# M868Hcjl.net
KiCad netlist of a schematic drawn in EAGLE
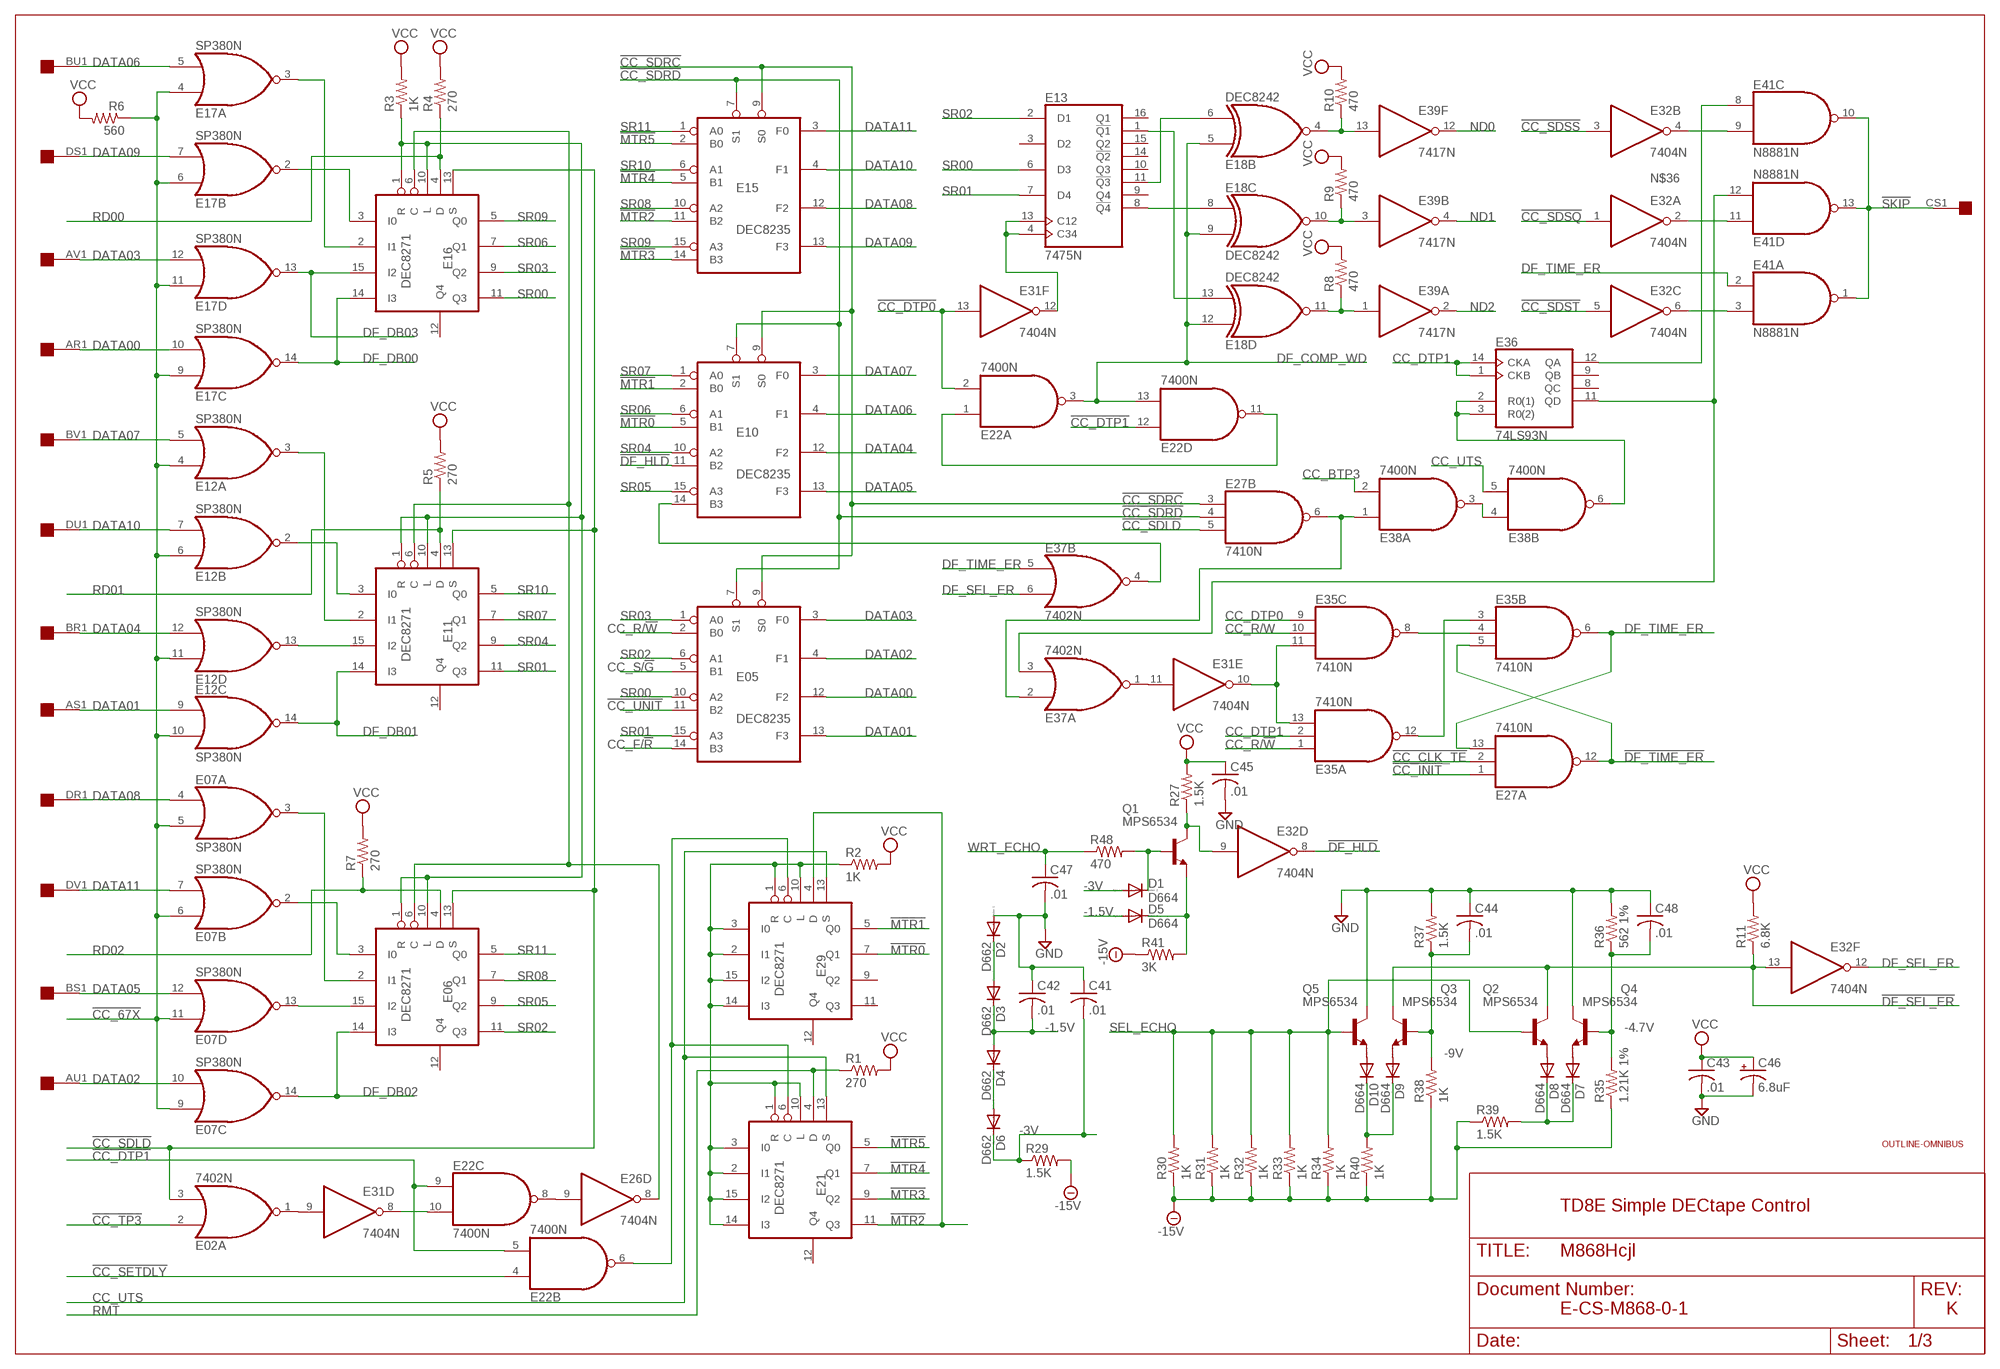
[diagram p0: schematic, sheet 1]
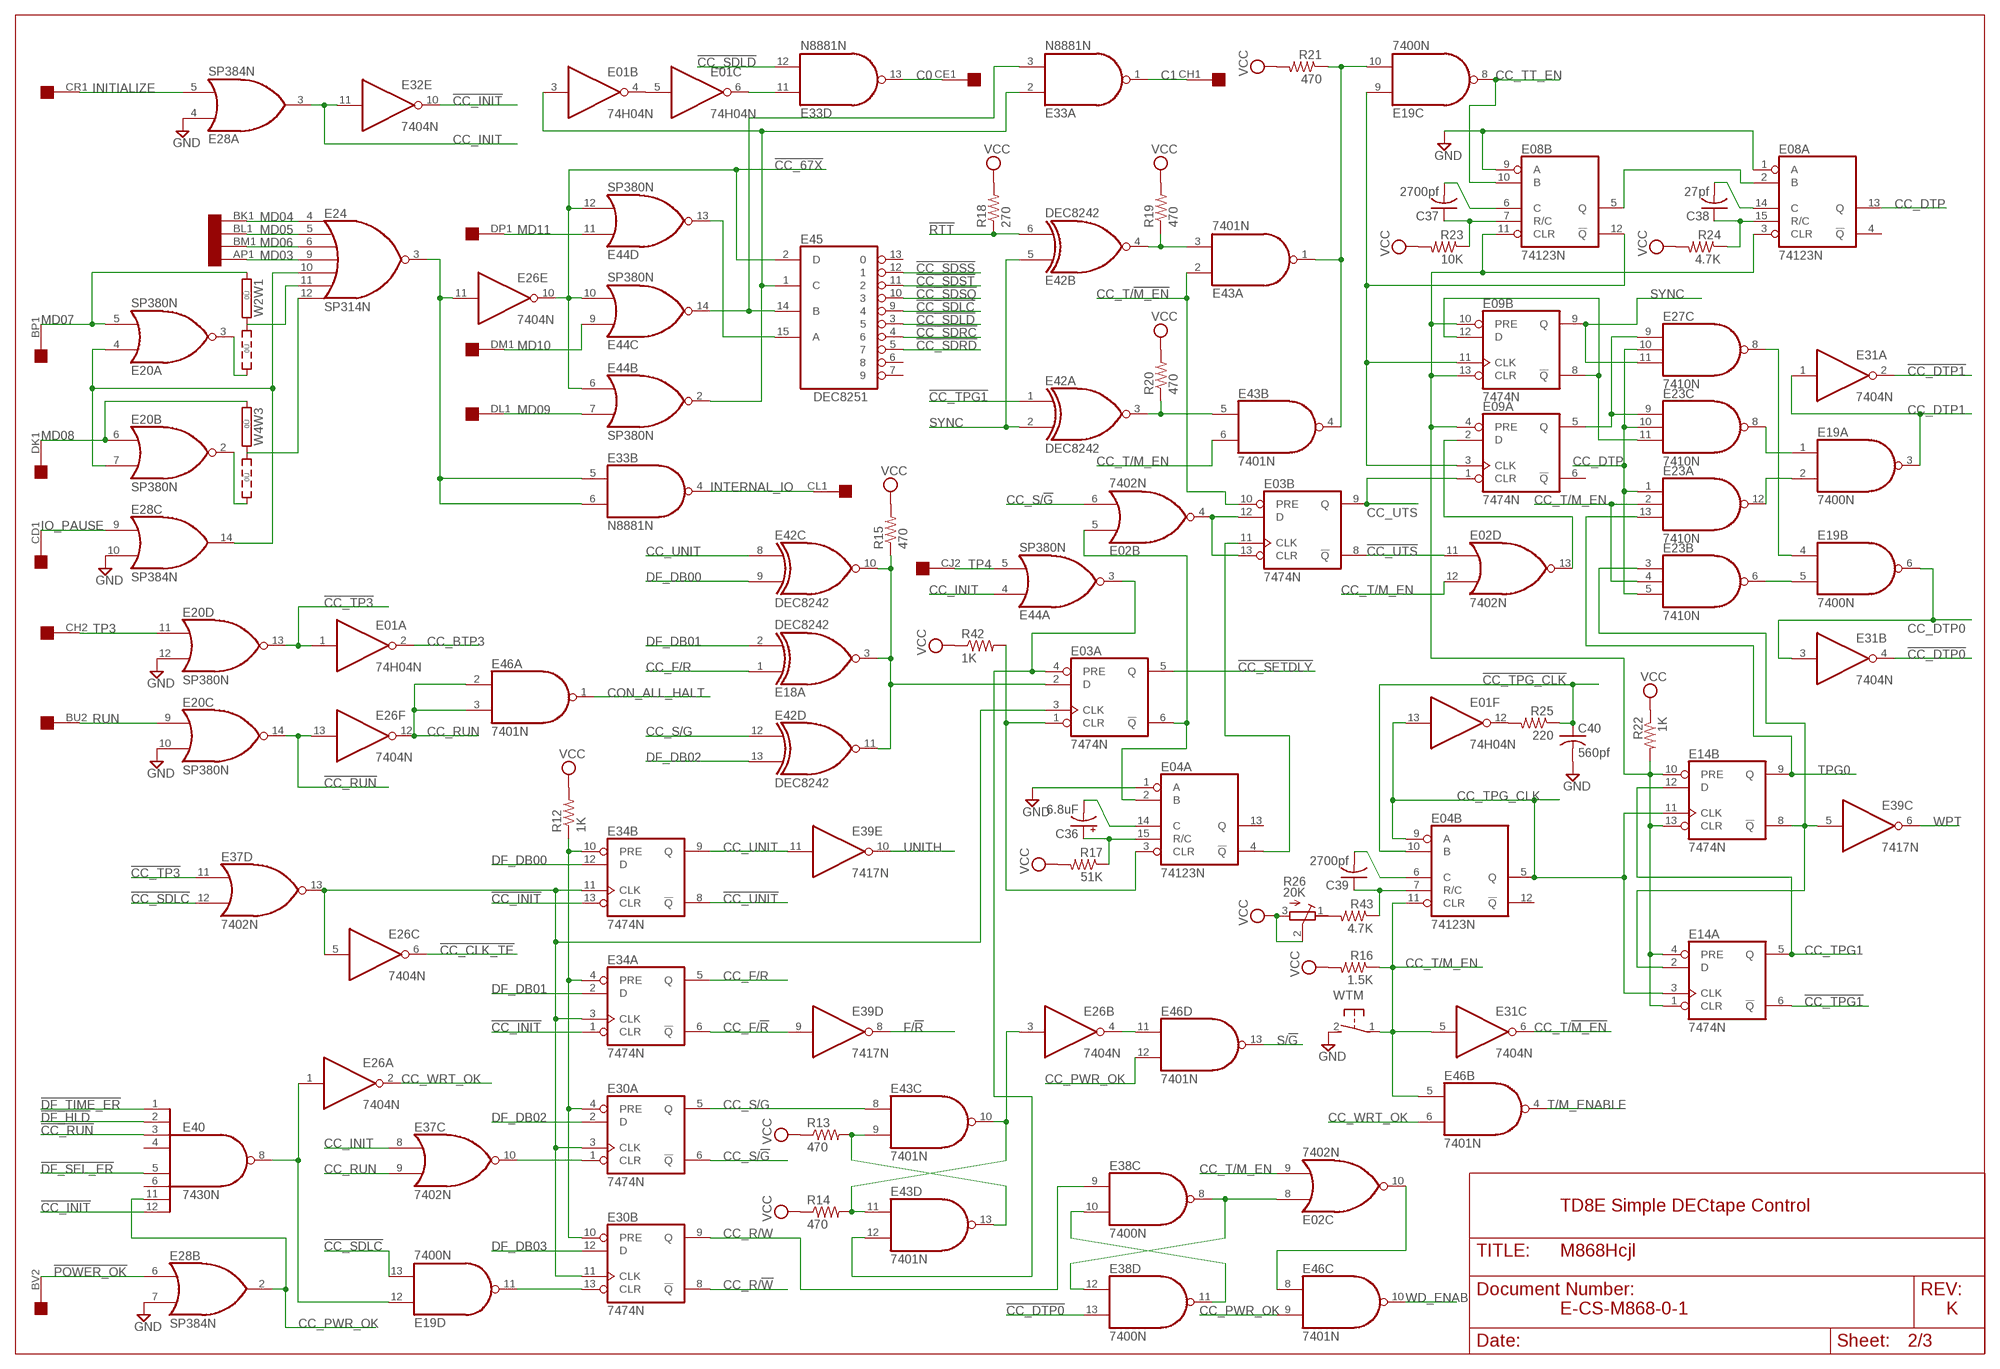
[diagram p1: schematic, sheet 2]
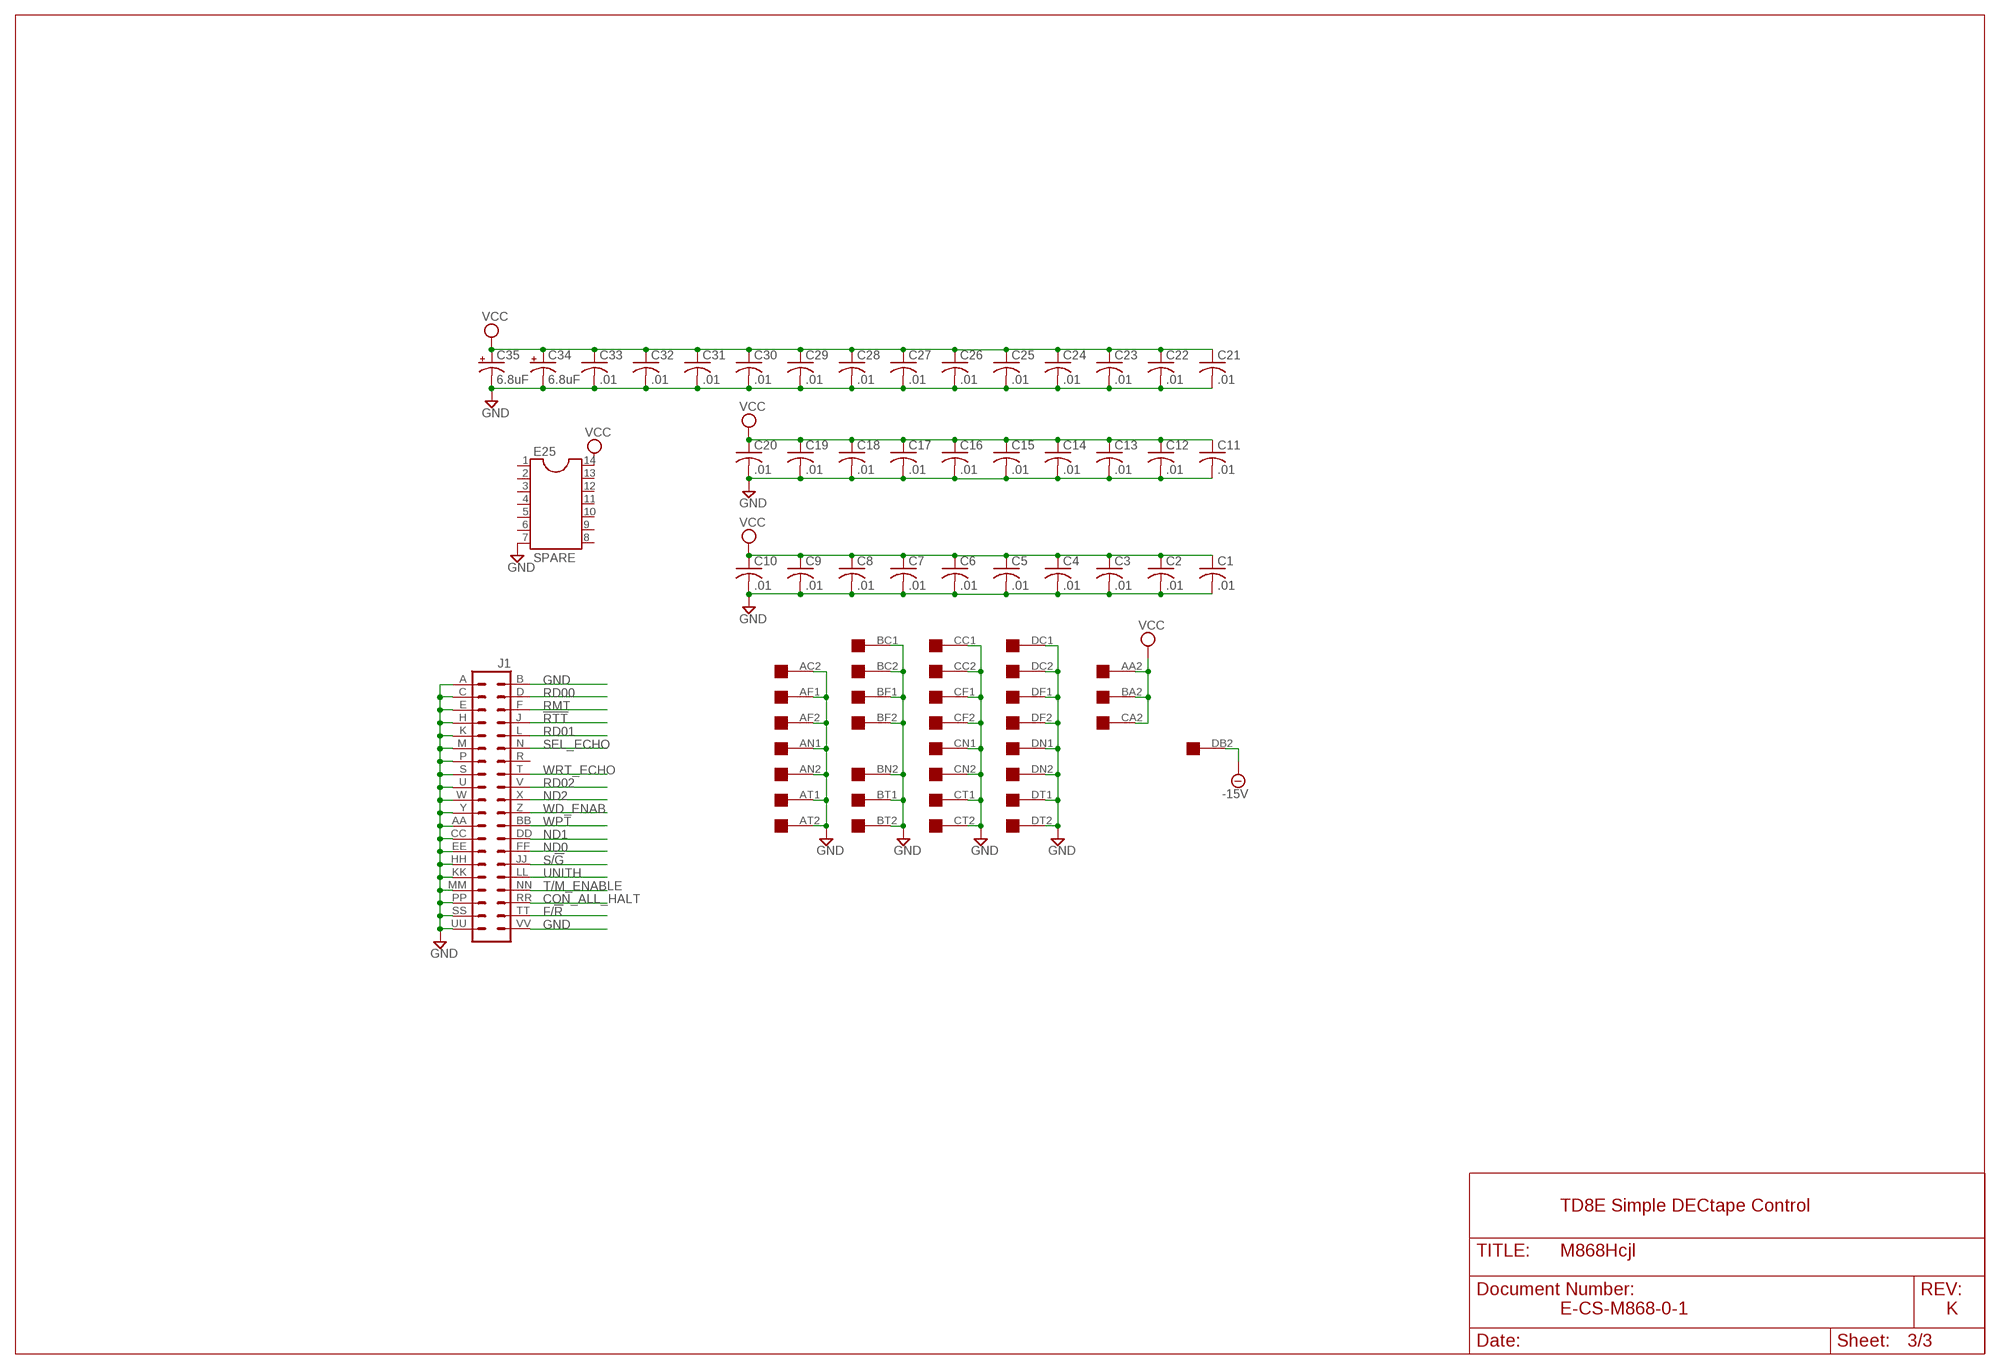
[diagram p2: schematic, sheet 3]

(export (version "E")
  (design (tool "Eeschema 10.0.6"))
  (components
    (comp (ref "C41")
      (value ".01")
      (footprint "eagle-import:C050-025X075")
      (libsource (lib "eagle-import") (part "C-US050-025X075"))
    )
    (comp (ref "C42")
      (value ".01")
      (footprint "eagle-import:C050-025X075")
      (libsource (lib "eagle-import") (part "C-US050-025X075"))
    )
    (comp (ref "C43")
      (value ".01")
      (footprint "eagle-import:C050-025X075")
      (libsource (lib "eagle-import") (part "C-US050-025X075"))
    )
    (comp (ref "C44")
      (value ".01")
      (footprint "eagle-import:C050-025X075")
      (libsource (lib "eagle-import") (part "C-US050-025X075"))
    )
    (comp (ref "C45")
      (value ".01")
      (footprint "eagle-import:C050-025X075")
      (libsource (lib "eagle-import") (part "C-US050-025X075"))
    )
    (comp (ref "C46")
      (value "6.8uF")
      (footprint "eagle-import:E12-8")
      (libsource (lib "eagle-import") (part "CPOL-USE20-8AXIAL"))
    )
    (comp (ref "C47")
      (value ".01")
      (footprint "eagle-import:C050-025X075")
      (libsource (lib "eagle-import") (part "C-US050-025X075"))
    )
    (comp (ref "C48")
      (value ".01")
      (footprint "eagle-import:C050-025X075")
      (libsource (lib "eagle-import") (part "C-US050-025X075"))
    )
    (comp (ref "D1")
      (value "D664")
      (footprint "eagle-import:DO35-10")
      (libsource (lib "eagle-import") (part "1N4148DO35-10"))
    )
    (comp (ref "D2")
      (value "D662")
      (footprint "eagle-import:DO35-10")
      (libsource (lib "eagle-import") (part "1N4148DO35-10"))
    )
    (comp (ref "D3")
      (value "D662")
      (footprint "eagle-import:DO35-10")
      (libsource (lib "eagle-import") (part "1N4148DO35-10"))
    )
    (comp (ref "D4")
      (value "D662")
      (footprint "eagle-import:DO35-10")
      (libsource (lib "eagle-import") (part "1N4148DO35-10"))
    )
    (comp (ref "D5")
      (value "D664")
      (footprint "eagle-import:DO35-10")
      (libsource (lib "eagle-import") (part "1N4148DO35-10"))
    )
    (comp (ref "D6")
      (value "D662")
      (footprint "eagle-import:DO35-10")
      (libsource (lib "eagle-import") (part "1N4148DO35-10"))
    )
    (comp (ref "D7")
      (value "D664")
      (footprint "eagle-import:DO35-10")
      (libsource (lib "eagle-import") (part "1N4148DO35-10"))
    )
    (comp (ref "D8")
      (value "D664")
      (footprint "eagle-import:DO35-10")
      (libsource (lib "eagle-import") (part "1N4148DO35-10"))
    )
    (comp (ref "D9")
      (value "D664")
      (footprint "eagle-import:DO35-10")
      (libsource (lib "eagle-import") (part "1N4148DO35-10"))
    )
    (comp (ref "D10")
      (value "D664")
      (footprint "eagle-import:DO35-10")
      (libsource (lib "eagle-import") (part "1N4148DO35-10"))
    )
    (comp (ref "E02")
      (value "7402N")
      (footprint "eagle-import:DIL14")
      (libsource (lib "eagle-import") (part "7402N"))
    )
    (comp (ref "E05")
      (value "DEC8235")
      (footprint "eagle-import:DIL16")
      (libsource (lib "eagle-import") (part "DEC8235"))
    )
    (comp (ref "E06")
      (value "DEC8271")
      (footprint "eagle-import:DIL16")
      (libsource (lib "eagle-import") (part "DEC8271"))
    )
    (comp (ref "E07")
      (value "SP380N")
      (footprint "eagle-import:DIL14")
      (libsource (lib "eagle-import") (part "SP380N"))
    )
    (comp (ref "E10")
      (value "DEC8235")
      (footprint "eagle-import:DIL16")
      (libsource (lib "eagle-import") (part "DEC8235"))
    )
    (comp (ref "E11")
      (value "DEC8271")
      (footprint "eagle-import:DIL16")
      (libsource (lib "eagle-import") (part "DEC8271"))
    )
    (comp (ref "E12")
      (value "SP380N")
      (footprint "eagle-import:DIL14")
      (libsource (lib "eagle-import") (part "SP380N"))
    )
    (comp (ref "E13")
      (value "7475N")
      (footprint "eagle-import:DIL16")
      (libsource (lib "eagle-import") (part "7475N"))
    )
    (comp (ref "E15")
      (value "DEC8235")
      (footprint "eagle-import:DIL16")
      (libsource (lib "eagle-import") (part "DEC8235"))
    )
    (comp (ref "E16")
      (value "DEC8271")
      (footprint "eagle-import:DIL16")
      (libsource (lib "eagle-import") (part "DEC8271"))
    )
    (comp (ref "E17")
      (value "SP380N")
      (footprint "eagle-import:DIL14")
      (libsource (lib "eagle-import") (part "SP380N"))
    )
    (comp (ref "E18")
      (value "DEC8242")
      (footprint "eagle-import:DIL14")
      (libsource (lib "eagle-import") (part "74266NLS"))
    )
    (comp (ref "E21")
      (value "DEC8271")
      (footprint "eagle-import:DIL16")
      (libsource (lib "eagle-import") (part "DEC8271"))
    )
    (comp (ref "E22")
      (value "7400N")
      (footprint "eagle-import:DIL14")
      (libsource (lib "eagle-import") (part "7400N"))
    )
    (comp (ref "E26")
      (value "7404N")
      (footprint "eagle-import:DIL14")
      (libsource (lib "eagle-import") (part "7404N"))
    )
    (comp (ref "E27")
      (value "7410N")
      (footprint "eagle-import:DIL14")
      (libsource (lib "eagle-import") (part "7410N"))
    )
    (comp (ref "E29")
      (value "DEC8271")
      (footprint "eagle-import:DIL16")
      (libsource (lib "eagle-import") (part "DEC8271"))
    )
    (comp (ref "E31")
      (value "7404N")
      (footprint "eagle-import:DIL14")
      (libsource (lib "eagle-import") (part "7404N"))
    )
    (comp (ref "E32")
      (value "7404N")
      (footprint "eagle-import:DIL14")
      (libsource (lib "eagle-import") (part "7404N"))
    )
    (comp (ref "E35")
      (value "7410N")
      (footprint "eagle-import:DIL14")
      (libsource (lib "eagle-import") (part "7410N"))
    )
    (comp (ref "E36")
      (value "74LS93N")
      (footprint "eagle-import:DIL14")
      (libsource (lib "eagle-import") (part "7493NLS"))
    )
    (comp (ref "E37")
      (value "7402N")
      (footprint "eagle-import:DIL14")
      (libsource (lib "eagle-import") (part "7402N"))
    )
    (comp (ref "E38")
      (value "7400N")
      (footprint "eagle-import:DIL14")
      (libsource (lib "eagle-import") (part "7400N"))
    )
    (comp (ref "E39")
      (value "7417N")
      (footprint "eagle-import:DIL14")
      (libsource (lib "eagle-import") (part "7417N"))
    )
    (comp (ref "E41")
      (value "N8881N")
      (footprint "eagle-import:DIL14")
      (libsource (lib "eagle-import") (part "N8881N"))
    )
    (comp (ref "EDGE$")
      (value "QUAD")
      (footprint "eagle-import:EDGE-CON8")
      (libsource (lib "eagle-import") (part "QUAD"))
    )
    (comp (ref "Q1")
      (value "MPS6534")
      (footprint "eagle-import:TO5")
      (libsource (lib "eagle-import") (part "2N2219"))
    )
    (comp (ref "Q2")
      (value "MPS6534")
      (footprint "eagle-import:TO5")
      (libsource (lib "eagle-import") (part "2N2219"))
    )
    (comp (ref "Q3")
      (value "MPS6534")
      (footprint "eagle-import:TO5")
      (libsource (lib "eagle-import") (part "2N2219"))
    )
    (comp (ref "Q4")
      (value "MPS6534")
      (footprint "eagle-import:TO5")
      (libsource (lib "eagle-import") (part "2N2219"))
    )
    (comp (ref "Q5")
      (value "MPS6534")
      (footprint "eagle-import:TO5")
      (libsource (lib "eagle-import") (part "2N2219"))
    )
    (comp (ref "R1")
      (value "270")
      (footprint "eagle-import:0207_10")
      (libsource (lib "eagle-import") (part "R-US_0207/10"))
    )
    (comp (ref "R2")
      (value "1K")
      (footprint "eagle-import:0207_10")
      (libsource (lib "eagle-import") (part "R-US_0207/10"))
    )
    (comp (ref "R3")
      (value "1K")
      (footprint "eagle-import:0207_10")
      (libsource (lib "eagle-import") (part "R-US_0207/10"))
    )
    (comp (ref "R4")
      (value "270")
      (footprint "eagle-import:0207_10")
      (libsource (lib "eagle-import") (part "R-US_0207/10"))
    )
    (comp (ref "R5")
      (value "270")
      (footprint "eagle-import:0207_10")
      (libsource (lib "eagle-import") (part "R-US_0207/10"))
    )
    (comp (ref "R6")
      (value "560")
      (footprint "eagle-import:0207_10")
      (libsource (lib "eagle-import") (part "R-US_0207/10"))
    )
    (comp (ref "R7")
      (value "270")
      (footprint "eagle-import:0207_10")
      (libsource (lib "eagle-import") (part "R-US_0207/10"))
    )
    (comp (ref "R8")
      (value "470")
      (footprint "eagle-import:0207_10")
      (libsource (lib "eagle-import") (part "R-US_0207/10"))
    )
    (comp (ref "R9")
      (value "470")
      (footprint "eagle-import:0207_10")
      (libsource (lib "eagle-import") (part "R-US_0207/10"))
    )
    (comp (ref "R10")
      (value "470")
      (footprint "eagle-import:0207_10")
      (libsource (lib "eagle-import") (part "R-US_0207/10"))
    )
    (comp (ref "R11")
      (value "6.8K")
      (footprint "eagle-import:0207_10")
      (libsource (lib "eagle-import") (part "R-US_0207/10"))
    )
    (comp (ref "R27")
      (value "1.5K")
      (footprint "eagle-import:0207_10")
      (libsource (lib "eagle-import") (part "R-US_0207/10"))
    )
    (comp (ref "R29")
      (value "1.5K")
      (footprint "eagle-import:0207_10")
      (libsource (lib "eagle-import") (part "R-US_0207/10"))
    )
    (comp (ref "R30")
      (value "1K")
      (footprint "eagle-import:0207_10")
      (libsource (lib "eagle-import") (part "R-US_0207/10"))
    )
    (comp (ref "R31")
      (value "1K")
      (footprint "eagle-import:0207_10")
      (libsource (lib "eagle-import") (part "R-US_0207/10"))
    )
    (comp (ref "R32")
      (value "1K")
      (footprint "eagle-import:0207_10")
      (libsource (lib "eagle-import") (part "R-US_0207/10"))
    )
    (comp (ref "R33")
      (value "1K")
      (footprint "eagle-import:0207_10")
      (libsource (lib "eagle-import") (part "R-US_0207/10"))
    )
    (comp (ref "R34")
      (value "1K")
      (footprint "eagle-import:0207_10")
      (libsource (lib "eagle-import") (part "R-US_0207/10"))
    )
    (comp (ref "R35")
      (value "1.21K 1%")
      (footprint "eagle-import:0207_15")
      (libsource (lib "eagle-import") (part "R-US_0207/15"))
    )
    (comp (ref "R36")
      (value "562 1%")
      (footprint "eagle-import:0207_15")
      (libsource (lib "eagle-import") (part "R-US_0207/15"))
    )
    (comp (ref "R37")
      (value "1.5K")
      (footprint "eagle-import:0207_10")
      (libsource (lib "eagle-import") (part "R-US_0207/10"))
    )
    (comp (ref "R38")
      (value "1K")
      (footprint "eagle-import:0207_10")
      (libsource (lib "eagle-import") (part "R-US_0207/10"))
    )
    (comp (ref "R39")
      (value "1.5K")
      (footprint "eagle-import:0207_10")
      (libsource (lib "eagle-import") (part "R-US_0207/10"))
    )
    (comp (ref "R40")
      (value "1K")
      (footprint "eagle-import:0207_10")
      (libsource (lib "eagle-import") (part "R-US_0207/10"))
    )
    (comp (ref "R41")
      (value "3K")
      (footprint "eagle-import:0207_10")
      (libsource (lib "eagle-import") (part "R-US_0207/10"))
    )
    (comp (ref "R48")
      (value "470")
      (footprint "eagle-import:0207_10")
      (libsource (lib "eagle-import") (part "R-US_0207/10"))
    )
    (comp (ref "U$1")
      (value "OUTLINE-OMNIBUS")
      (footprint "eagle-import:OMNIBUS")
      (libsource (lib "eagle-import") (part "OUTLINE-OMNIBUS"))
    )
    (comp (ref "C1")
      (value ".01")
      (footprint "eagle-import:C050-025X075")
      (libsource (lib "eagle-import") (part "C-US050-025X075"))
    )
    (comp (ref "C2")
      (value ".01")
      (footprint "eagle-import:C050-025X075")
      (libsource (lib "eagle-import") (part "C-US050-025X075"))
    )
    (comp (ref "C3")
      (value ".01")
      (footprint "eagle-import:C050-025X075")
      (libsource (lib "eagle-import") (part "C-US050-025X075"))
    )
    (comp (ref "C4")
      (value ".01")
      (footprint "eagle-import:C050-025X075")
      (libsource (lib "eagle-import") (part "C-US050-025X075"))
    )
    (comp (ref "C5")
      (value ".01")
      (footprint "eagle-import:C050-025X075")
      (libsource (lib "eagle-import") (part "C-US050-025X075"))
    )
    (comp (ref "C6")
      (value ".01")
      (footprint "eagle-import:C050-025X075")
      (libsource (lib "eagle-import") (part "C-US050-025X075"))
    )
    (comp (ref "C7")
      (value ".01")
      (footprint "eagle-import:C050-025X075")
      (libsource (lib "eagle-import") (part "C-US050-025X075"))
    )
    (comp (ref "C8")
      (value ".01")
      (footprint "eagle-import:C050-025X075")
      (libsource (lib "eagle-import") (part "C-US050-025X075"))
    )
    (comp (ref "C9")
      (value ".01")
      (footprint "eagle-import:C050-025X075")
      (libsource (lib "eagle-import") (part "C-US050-025X075"))
    )
    (comp (ref "C10")
      (value ".01")
      (footprint "eagle-import:C050-025X075")
      (libsource (lib "eagle-import") (part "C-US050-025X075"))
    )
    (comp (ref "C11")
      (value ".01")
      (footprint "eagle-import:C050-025X075")
      (libsource (lib "eagle-import") (part "C-US050-025X075"))
    )
    (comp (ref "C12")
      (value ".01")
      (footprint "eagle-import:C050-025X075")
      (libsource (lib "eagle-import") (part "C-US050-025X075"))
    )
    (comp (ref "C13")
      (value ".01")
      (footprint "eagle-import:C050-025X075")
      (libsource (lib "eagle-import") (part "C-US050-025X075"))
    )
    (comp (ref "C14")
      (value ".01")
      (footprint "eagle-import:C050-025X075")
      (libsource (lib "eagle-import") (part "C-US050-025X075"))
    )
    (comp (ref "C15")
      (value ".01")
      (footprint "eagle-import:C050-025X075")
      (libsource (lib "eagle-import") (part "C-US050-025X075"))
    )
    (comp (ref "C16")
      (value ".01")
      (footprint "eagle-import:C050-025X075")
      (libsource (lib "eagle-import") (part "C-US050-025X075"))
    )
    (comp (ref "C17")
      (value ".01")
      (footprint "eagle-import:C050-025X075")
      (libsource (lib "eagle-import") (part "C-US050-025X075"))
    )
    (comp (ref "C18")
      (value ".01")
      (footprint "eagle-import:C050-025X075")
      (libsource (lib "eagle-import") (part "C-US050-025X075"))
    )
    (comp (ref "C19")
      (value ".01")
      (footprint "eagle-import:C050-025X075")
      (libsource (lib "eagle-import") (part "C-US050-025X075"))
    )
    (comp (ref "C20")
      (value ".01")
      (footprint "eagle-import:C050-025X075")
      (libsource (lib "eagle-import") (part "C-US050-025X075"))
    )
    (comp (ref "C21")
      (value ".01")
      (footprint "eagle-import:C050-025X075")
      (libsource (lib "eagle-import") (part "C-US050-025X075"))
    )
    (comp (ref "C22")
      (value ".01")
      (footprint "eagle-import:C050-025X075")
      (libsource (lib "eagle-import") (part "C-US050-025X075"))
    )
    (comp (ref "C23")
      (value ".01")
      (footprint "eagle-import:C050-025X075")
      (libsource (lib "eagle-import") (part "C-US050-025X075"))
    )
    (comp (ref "C24")
      (value ".01")
      (footprint "eagle-import:C050-025X075")
      (libsource (lib "eagle-import") (part "C-US050-025X075"))
    )
    (comp (ref "C25")
      (value ".01")
      (footprint "eagle-import:C050-025X075")
      (libsource (lib "eagle-import") (part "C-US050-025X075"))
    )
    (comp (ref "C26")
      (value ".01")
      (footprint "eagle-import:C050-025X075")
      (libsource (lib "eagle-import") (part "C-US050-025X075"))
    )
    (comp (ref "C27")
      (value ".01")
      (footprint "eagle-import:C050-025X075")
      (libsource (lib "eagle-import") (part "C-US050-025X075"))
    )
    (comp (ref "C28")
      (value ".01")
      (footprint "eagle-import:C050-025X075")
      (libsource (lib "eagle-import") (part "C-US050-025X075"))
    )
    (comp (ref "C29")
      (value ".01")
      (footprint "eagle-import:C050-025X075")
      (libsource (lib "eagle-import") (part "C-US050-025X075"))
    )
    (comp (ref "C30")
      (value ".01")
      (footprint "eagle-import:C050-025X075")
      (libsource (lib "eagle-import") (part "C-US050-025X075"))
    )
    (comp (ref "C31")
      (value ".01")
      (footprint "eagle-import:C050-025X075")
      (libsource (lib "eagle-import") (part "C-US050-025X075"))
    )
    (comp (ref "C32")
      (value ".01")
      (footprint "eagle-import:C050-025X075")
      (libsource (lib "eagle-import") (part "C-US050-025X075"))
    )
    (comp (ref "C33")
      (value ".01")
      (footprint "eagle-import:C050-025X075")
      (libsource (lib "eagle-import") (part "C-US050-025X075"))
    )
    (comp (ref "C34")
      (value "6.8uF")
      (footprint "eagle-import:E12-8")
      (libsource (lib "eagle-import") (part "CPOL-USE20-8AXIAL"))
    )
    (comp (ref "C35")
      (value "6.8uF")
      (footprint "eagle-import:E12-8")
      (libsource (lib "eagle-import") (part "CPOL-USE20-8AXIAL"))
    )
    (comp (ref "E25")
      (value "SPARE")
      (footprint "eagle-import:DIL14")
      (libsource (lib "eagle-import") (part "DIL14"))
    )
    (comp (ref "J1")
      (value "DEC40PINH")
      (footprint "eagle-import:DEC40PINH")
      (libsource (lib "eagle-import") (part "DEC40PINH"))
    )
    (comp (ref "C36")
      (value "6.8uF")
      (footprint "eagle-import:E12-8")
      (libsource (lib "eagle-import") (part "CPOL-USE20-8AXIAL"))
    )
    (comp (ref "C37")
      (value "2700pf")
      (footprint "eagle-import:C102-043X133")
      (libsource (lib "eagle-import") (part "C-US102-043X133"))
    )
    (comp (ref "C38")
      (value "27pf")
      (footprint "eagle-import:C050-025X075")
      (libsource (lib "eagle-import") (part "C-US050-025X075"))
    )
    (comp (ref "C39")
      (value "2700pf")
      (footprint "eagle-import:C102-043X133")
      (libsource (lib "eagle-import") (part "C-US102-043X133"))
    )
    (comp (ref "C40")
      (value "560pf")
      (footprint "eagle-import:C075-032X103")
      (libsource (lib "eagle-import") (part "C-US075-032X103"))
    )
    (comp (ref "E01")
      (value "74H04N")
      (footprint "eagle-import:DIL14")
      (libsource (lib "eagle-import") (part "7404NS"))
    )
    (comp (ref "E03")
      (value "7474N")
      (footprint "eagle-import:DIL14")
      (libsource (lib "eagle-import") (part "7474NS"))
    )
    (comp (ref "E04")
      (value "74123N")
      (footprint "eagle-import:DIL16")
      (libsource (lib "eagle-import") (part "74123N"))
    )
    (comp (ref "E08")
      (value "74123N")
      (footprint "eagle-import:DIL16")
      (libsource (lib "eagle-import") (part "74123N"))
    )
    (comp (ref "E09")
      (value "7474N")
      (footprint "eagle-import:DIL14")
      (libsource (lib "eagle-import") (part "7474NS"))
    )
    (comp (ref "E14")
      (value "7474N")
      (footprint "eagle-import:DIL14")
      (libsource (lib "eagle-import") (part "7474NS"))
    )
    (comp (ref "E19")
      (value "7400N")
      (footprint "eagle-import:DIL14")
      (libsource (lib "eagle-import") (part "7400N"))
    )
    (comp (ref "E20")
      (value "SP380N")
      (footprint "eagle-import:DIL14")
      (libsource (lib "eagle-import") (part "SP380N"))
    )
    (comp (ref "E23")
      (value "7410N")
      (footprint "eagle-import:DIL14")
      (libsource (lib "eagle-import") (part "7410N"))
    )
    (comp (ref "E24")
      (value "SP314N")
      (footprint "eagle-import:DIL14")
      (libsource (lib "eagle-import") (part "SP314N"))
    )
    (comp (ref "E28")
      (value "SP384N")
      (footprint "eagle-import:DIL14")
      (libsource (lib "eagle-import") (part "SP384N"))
    )
    (comp (ref "E30")
      (value "7474N")
      (footprint "eagle-import:DIL14")
      (libsource (lib "eagle-import") (part "7474NS"))
    )
    (comp (ref "E33")
      (value "N8881N")
      (footprint "eagle-import:DIL14")
      (libsource (lib "eagle-import") (part "N8881N"))
    )
    (comp (ref "E34")
      (value "7474N")
      (footprint "eagle-import:DIL14")
      (libsource (lib "eagle-import") (part "7474NS"))
    )
    (comp (ref "E40")
      (value "7430N")
      (footprint "eagle-import:DIL14")
      (libsource (lib "eagle-import") (part "7430N"))
    )
    (comp (ref "E42")
      (value "DEC8242")
      (footprint "eagle-import:DIL14")
      (libsource (lib "eagle-import") (part "74266NLS"))
    )
    (comp (ref "E43")
      (value "7401N")
      (footprint "eagle-import:DIL14")
      (libsource (lib "eagle-import") (part "7401NLS"))
    )
    (comp (ref "E44")
      (value "SP380N")
      (footprint "eagle-import:DIL14")
      (libsource (lib "eagle-import") (part "SP380N"))
    )
    (comp (ref "E45")
      (value "DEC8251")
      (footprint "eagle-import:DIL16")
      (libsource (lib "eagle-import") (part "DEC8251"))
    )
    (comp (ref "E46")
      (value "7401N")
      (footprint "eagle-import:DIL14")
      (libsource (lib "eagle-import") (part "7401NLS"))
    )
    (comp (ref "R12")
      (value "1K")
      (footprint "eagle-import:0207_10")
      (libsource (lib "eagle-import") (part "R-US_0207/10"))
    )
    (comp (ref "R13")
      (value "470")
      (footprint "eagle-import:0207_10")
      (libsource (lib "eagle-import") (part "R-US_0207/10"))
    )
    (comp (ref "R14")
      (value "470")
      (footprint "eagle-import:0207_10")
      (libsource (lib "eagle-import") (part "R-US_0207/10"))
    )
    (comp (ref "R15")
      (value "470")
      (footprint "eagle-import:0207_10")
      (libsource (lib "eagle-import") (part "R-US_0207/10"))
    )
    (comp (ref "R16")
      (value "1.5K")
      (footprint "eagle-import:0207_10")
      (libsource (lib "eagle-import") (part "R-US_0207/10"))
    )
    (comp (ref "R17")
      (value "51K")
      (footprint "eagle-import:0207_10")
      (libsource (lib "eagle-import") (part "R-US_0207/10"))
    )
    (comp (ref "R18")
      (value "270")
      (footprint "eagle-import:0207_10")
      (libsource (lib "eagle-import") (part "R-US_0207/10"))
    )
    (comp (ref "R19")
      (value "470")
      (footprint "eagle-import:0207_10")
      (libsource (lib "eagle-import") (part "R-US_0207/10"))
    )
    (comp (ref "R20")
      (value "470")
      (footprint "eagle-import:0207_10")
      (libsource (lib "eagle-import") (part "R-US_0207/10"))
    )
    (comp (ref "R21")
      (value "470")
      (footprint "eagle-import:0207_10")
      (libsource (lib "eagle-import") (part "R-US_0207/10"))
    )
    (comp (ref "R22")
      (value "1K")
      (footprint "eagle-import:0207_10")
      (libsource (lib "eagle-import") (part "R-US_0207/10"))
    )
    (comp (ref "R23")
      (value "10K")
      (footprint "eagle-import:0207_10")
      (libsource (lib "eagle-import") (part "R-US_0207/10"))
    )
    (comp (ref "R24")
      (value "4.7K")
      (footprint "eagle-import:0207_10")
      (libsource (lib "eagle-import") (part "R-US_0207/10"))
    )
    (comp (ref "R25")
      (value "220")
      (footprint "eagle-import:0207_10")
      (libsource (lib "eagle-import") (part "R-US_0207/10"))
    )
    (comp (ref "R26")
      (value "20K")
      (footprint "eagle-import:3006Y")
      (libsource (lib "eagle-import") (part "275P"))
    )
    (comp (ref "R42")
      (value "1K")
      (footprint "eagle-import:0207_10")
      (libsource (lib "eagle-import") (part "R-US_0207/10"))
    )
    (comp (ref "R43")
      (value "4.7K")
      (footprint "eagle-import:0207_10")
      (libsource (lib "eagle-import") (part "R-US_0207/10"))
    )
    (comp (ref "W2W1")
      (value "0R2")
      (footprint "eagle-import:0R2_10")
      (libsource (lib "eagle-import") (part "0R2"))
    )
    (comp (ref "W4W3")
      (value "0R2")
      (footprint "eagle-import:0R2_10")
      (libsource (lib "eagle-import") (part "0R2"))
    )
    (comp (ref "WTM")
      (value "31-XX")
      (footprint "eagle-import:B3F-31XX")
      (fields (field (name "MPN") "B3F-3100"))
      (libsource (lib "eagle-import") (part "31-XX"))
    )
  )
  (nets
    (net (code "1") (name "-1.5V") (class "Default")
      (node (ref "C42") (pin "2") (pinfunction "2_2") (pintype "passive"))
      (node (ref "D3") (pin "C") (pinfunction "C_C") (pintype "passive"))
      (node (ref "D4") (pin "A") (pinfunction "A_A") (pintype "passive"))
      (node (ref "D5") (pin "A") (pinfunction "A_A") (pintype "passive"))
    )
    (net (code "2") (name "-3V") (class "Default")
      (node (ref "C41") (pin "2") (pinfunction "2_2") (pintype "passive"))
      (node (ref "D1") (pin "A") (pinfunction "A_A") (pintype "passive"))
      (node (ref "D6") (pin "C") (pinfunction "C_C") (pintype "passive"))
      (node (ref "R29") (pin "1") (pinfunction "1_1") (pintype "passive"))
    )
    (net (code "3") (name "-4.7V") (class "Default")
      (node (ref "C48") (pin "2") (pinfunction "2_2") (pintype "passive"))
      (node (ref "Q4") (pin "2") (pinfunction "B_2") (pintype "passive"))
      (node (ref "R35") (pin "2") (pinfunction "2_2") (pintype "passive"))
      (node (ref "R36") (pin "1") (pinfunction "1_1") (pintype "passive"))
    )
    (net (code "4") (name "-9V") (class "Default")
      (node (ref "C44") (pin "2") (pinfunction "2_2") (pintype "passive"))
      (node (ref "Q3") (pin "2") (pinfunction "B_2") (pintype "passive"))
      (node (ref "R37") (pin "1") (pinfunction "1_1") (pintype "passive"))
      (node (ref "R38") (pin "2") (pinfunction "2_2") (pintype "passive"))
    )
    (net (code "5") (name "-15V") (class "Default")
      (node (ref "EDGE$") (pin "DB2") (pinfunction "1_DB2") (pintype "bidirectional"))
      (node (ref "R29") (pin "2") (pinfunction "2_2") (pintype "passive"))
      (node (ref "R30") (pin "1") (pinfunction "1_1") (pintype "passive"))
      (node (ref "R31") (pin "1") (pinfunction "1_1") (pintype "passive"))
      (node (ref "R32") (pin "1") (pinfunction "1_1") (pintype "passive"))
      (node (ref "R33") (pin "1") (pinfunction "1_1") (pintype "passive"))
      (node (ref "R34") (pin "1") (pinfunction "1_1") (pintype "passive"))
      (node (ref "R35") (pin "1") (pinfunction "1_1") (pintype "passive"))
      (node (ref "R38") (pin "1") (pinfunction "1_1") (pintype "passive"))
      (node (ref "R39") (pin "1") (pinfunction "1_1") (pintype "passive"))
      (node (ref "R40") (pin "1") (pinfunction "1_1") (pintype "passive"))
      (node (ref "R41") (pin "1") (pinfunction "1_1") (pintype "passive"))
    )
    (net (code "6") (name "C0") (class "Default")
      (node (ref "E33") (pin "13") (pinfunction "O_13") (pintype "open_collector"))
      (node (ref "EDGE$") (pin "CE1") (pinfunction "1_CE1") (pintype "bidirectional"))
    )
    (net (code "7") (name "C1") (class "Default")
      (node (ref "E33") (pin "1") (pinfunction "O_1") (pintype "open_collector"))
      (node (ref "EDGE$") (pin "CH1") (pinfunction "1_CH1") (pintype "bidirectional"))
    )
    (net (code "8") (name "CC_BTP3") (class "Default")
      (node (ref "E01") (pin "2") (pinfunction "O_2") (pintype "output"))
      (node (ref "E38") (pin "2") (pinfunction "I1_2") (pintype "input"))
    )
    (net (code "9") (name "CC_DTP") (class "Default")
      (node (ref "E08") (pin "13") (pinfunction "Q_13") (pintype "output"))
      (node (ref "E23") (pin "1") (pinfunction "I0_1") (pintype "input"))
      (node (ref "E23") (pin "10") (pinfunction "I1_10") (pintype "input"))
      (node (ref "E23") (pin "5") (pinfunction "I2_5") (pintype "input"))
      (node (ref "E27") (pin "10") (pinfunction "I1_10") (pintype "input"))
    )
    (net (code "10") (name "CC_DTP0") (class "Default")
      (node (ref "E19") (pin "6") (pinfunction "O_6") (pintype "output"))
      (node (ref "E31") (pin "3") (pinfunction "I_3") (pintype "input"))
      (node (ref "E35") (pin "9") (pinfunction "I0_9") (pintype "input"))
    )
    (net (code "11") (name "CC_DTP1") (class "Default")
      (node (ref "E19") (pin "3") (pinfunction "O_3") (pintype "output"))
      (node (ref "E31") (pin "1") (pinfunction "I_1") (pintype "input"))
      (node (ref "E35") (pin "2") (pinfunction "I1_2") (pintype "input"))
      (node (ref "E36") (pin "1") (pinfunction "CKB_1") (pintype "input"))
      (node (ref "E36") (pin "14") (pinfunction "CKA_14") (pintype "input"))
    )
    (net (code "12") (name "CC_F{slash}R") (class "Default")
      (node (ref "E18") (pin "1") (pinfunction "I0_1") (pintype "input"))
      (node (ref "E34") (pin "5") (pinfunction "Q_5") (pintype "output"))
    )
    (net (code "13") (name "CC_F{slash}~{R}") (class "Default")
      (node (ref "E05") (pin "14") (pinfunction "B3_14") (pintype "input"))
      (node (ref "E34") (pin "6") (pinfunction "~{Q}_6") (pintype "output"))
      (node (ref "E39") (pin "9") (pinfunction "I_9") (pintype "input"))
    )
    (net (code "14") (name "CC_INIT") (class "Default")
      (node (ref "E28") (pin "3") (pinfunction "O_3") (pintype "output"))
      (node (ref "E32") (pin "11") (pinfunction "I_11") (pintype "input"))
      (node (ref "E37") (pin "8") (pinfunction "I0_8") (pintype "input"))
      (node (ref "E44") (pin "4") (pinfunction "I0_4") (pintype "input"))
    )
    (net (code "15") (name "CC_PWR_OK") (class "Default")
      (node (ref "E28") (pin "2") (pinfunction "O_2") (pintype "output"))
      (node (ref "E40") (pin "11") (pinfunction "I6_11") (pintype "input"))
      (node (ref "E46") (pin "12") (pinfunction "I1_12") (pintype "input"))
      (node (ref "E46") (pin "9") (pinfunction "I1_9") (pintype "input"))
    )
    (net (code "16") (name "CC_RUN") (class "Default")
      (node (ref "E26") (pin "12") (pinfunction "O_12") (pintype "output"))
      (node (ref "E37") (pin "9") (pinfunction "I1_9") (pintype "input"))
      (node (ref "E46") (pin "2") (pinfunction "I0_2") (pintype "input"))
      (node (ref "E46") (pin "3") (pinfunction "I1_3") (pintype "input"))
    )
    (net (code "17") (name "CC_R{slash}W") (class "Default")
      (node (ref "E30") (pin "9") (pinfunction "Q_9") (pintype "output"))
      (node (ref "E35") (pin "10") (pinfunction "I1_10") (pintype "input"))
      (node (ref "E38") (pin "9") (pinfunction "I0_9") (pintype "input"))
    )
    (net (code "18") (name "CC_R{slash}~{W}") (class "Default")
      (node (ref "E05") (pin "2") (pinfunction "B0_2") (pintype "input"))
      (node (ref "E30") (pin "8") (pinfunction "~{Q}_8") (pintype "output"))
      (node (ref "E35") (pin "1") (pinfunction "I0_1") (pintype "input"))
    )
    (net (code "19") (name "CC_S{slash}G") (class "Default")
      (node (ref "E30") (pin "5") (pinfunction "Q_5") (pintype "output"))
      (node (ref "E42") (pin "12") (pinfunction "I0_12") (pintype "input"))
      (node (ref "E43") (pin "8") (pinfunction "I0_8") (pintype "input"))
    )
    (net (code "20") (name "CC_S{slash}~{G}") (class "Default")
      (node (ref "E02") (pin "6") (pinfunction "I1_6") (pintype "input"))
      (node (ref "E05") (pin "5") (pinfunction "B1_5") (pintype "input"))
      (node (ref "E30") (pin "6") (pinfunction "~{Q}_6") (pintype "output"))
    )
    (net (code "21") (name "CC_TPG1") (class "Default")
      (node (ref "E14") (pin "12") (pinfunction "D_12") (pintype "input"))
      (node (ref "E14") (pin "5") (pinfunction "Q_5") (pintype "output"))
    )
    (net (code "22") (name "CC_TPG_CLK") (class "Default")
      (node (ref "E01") (pin "13") (pinfunction "I_13") (pintype "input"))
      (node (ref "E04") (pin "5") (pinfunction "Q_5") (pintype "output"))
      (node (ref "E04") (pin "9") (pinfunction "A_9") (pintype "input"))
      (node (ref "E14") (pin "11") (pinfunction "CLK_11") (pintype "input"))
      (node (ref "E14") (pin "3") (pinfunction "CLK_3") (pintype "input"))
    )
    (net (code "23") (name "CC_TT_EN") (class "Default")
      (node (ref "E08") (pin "10") (pinfunction "B_10") (pintype "input"))
      (node (ref "E19") (pin "8") (pinfunction "O_8") (pintype "output"))
    )
    (net (code "24") (name "CC_T{slash}M_EN") (class "Default")
      (node (ref "E02") (pin "12") (pinfunction "I1_12") (pintype "input"))
      (node (ref "E02") (pin "9") (pinfunction "I1_9") (pintype "input"))
      (node (ref "E04") (pin "11") (pinfunction "CLR_11") (pintype "input"))
      (node (ref "E23") (pin "2") (pinfunction "I1_2") (pintype "input"))
      (node (ref "E23") (pin "4") (pinfunction "I1_4") (pintype "input"))
      (node (ref "E31") (pin "5") (pinfunction "I_5") (pintype "input"))
      (node (ref "E43") (pin "6") (pinfunction "I1_6") (pintype "input"))
      (node (ref "E46") (pin "5") (pinfunction "I0_5") (pintype "input"))
      (node (ref "R16") (pin "1") (pinfunction "1_1") (pintype "passive"))
      (node (ref "WTM") (pin "1") (pinfunction "P_1") (pintype "passive"))
    )
    (net (code "25") (name "CC_T{slash}~{M_EN}") (class "Default")
      (node (ref "E03") (pin "10") (pinfunction "PRE_10") (pintype "input"))
      (node (ref "E31") (pin "6") (pinfunction "O_6") (pintype "output"))
      (node (ref "E43") (pin "2") (pinfunction "I0_2") (pintype "input"))
    )
    (net (code "26") (name "CC_UNIT") (class "Default")
      (node (ref "E34") (pin "9") (pinfunction "Q_9") (pintype "output"))
      (node (ref "E39") (pin "11") (pinfunction "I_11") (pintype "input"))
      (node (ref "E42") (pin "8") (pinfunction "I0_8") (pintype "input"))
    )
    (net (code "27") (name "CC_UTS") (class "Default")
      (node (ref "E03") (pin "9") (pinfunction "Q_9") (pintype "output"))
      (node (ref "E09") (pin "1") (pinfunction "CLR_1") (pintype "input"))
      (node (ref "E21") (pin "13") (pinfunction "S_13") (pintype "input"))
      (node (ref "E29") (pin "13") (pinfunction "S_13") (pintype "input"))
      (node (ref "E38") (pin "5") (pinfunction "I1_5") (pintype "input"))
    )
    (net (code "28") (name "CC_WRT_OK") (class "Default")
      (node (ref "E26") (pin "2") (pinfunction "O_2") (pintype "output"))
      (node (ref "E46") (pin "6") (pinfunction "I1_6") (pintype "input"))
    )
    (net (code "29") (name "CON_ALL_HALT") (class "Default")
      (node (ref "E46") (pin "1") (pinfunction "O_1") (pintype "open_collector"))
      (node (ref "J1") (pin "RR") (pinfunction "36_RR") (pintype "bidirectional"))
    )
    (net (code "30") (name "DATA00") (class "Default")
      (node (ref "E05") (pin "12") (pinfunction "F2_12") (pintype "open_collector"))
      (node (ref "E17") (pin "10") (pinfunction "I1_10") (pintype "input"))
      (node (ref "EDGE$") (pin "AR1") (pinfunction "1_AR1") (pintype "bidirectional"))
    )
    (net (code "31") (name "DATA01") (class "Default")
      (node (ref "E05") (pin "13") (pinfunction "F3_13") (pintype "open_collector"))
      (node (ref "E12") (pin "9") (pinfunction "I0_9") (pintype "input"))
      (node (ref "EDGE$") (pin "AS1") (pinfunction "1_AS1") (pintype "bidirectional"))
    )
    (net (code "32") (name "DATA02") (class "Default")
      (node (ref "E05") (pin "4") (pinfunction "F1_4") (pintype "open_collector"))
      (node (ref "E07") (pin "10") (pinfunction "I1_10") (pintype "input"))
      (node (ref "EDGE$") (pin "AU1") (pinfunction "1_AU1") (pintype "bidirectional"))
    )
    (net (code "33") (name "DATA03") (class "Default")
      (node (ref "E05") (pin "3") (pinfunction "F0_3") (pintype "open_collector"))
      (node (ref "E17") (pin "12") (pinfunction "I1_12") (pintype "input"))
      (node (ref "EDGE$") (pin "AV1") (pinfunction "1_AV1") (pintype "bidirectional"))
    )
    (net (code "34") (name "DATA04") (class "Default")
      (node (ref "E10") (pin "12") (pinfunction "F2_12") (pintype "open_collector"))
      (node (ref "E12") (pin "12") (pinfunction "I1_12") (pintype "input"))
      (node (ref "EDGE$") (pin "BR1") (pinfunction "1_BR1") (pintype "bidirectional"))
    )
    (net (code "35") (name "DATA05") (class "Default")
      (node (ref "E07") (pin "12") (pinfunction "I1_12") (pintype "input"))
      (node (ref "E10") (pin "13") (pinfunction "F3_13") (pintype "open_collector"))
      (node (ref "EDGE$") (pin "BS1") (pinfunction "1_BS1") (pintype "bidirectional"))
    )
    (net (code "36") (name "DATA06") (class "Default")
      (node (ref "E10") (pin "4") (pinfunction "F1_4") (pintype "open_collector"))
      (node (ref "E17") (pin "5") (pinfunction "I1_5") (pintype "input"))
      (node (ref "EDGE$") (pin "BU1") (pinfunction "1_BU1") (pintype "bidirectional"))
    )
    (net (code "37") (name "DATA07") (class "Default")
      (node (ref "E10") (pin "3") (pinfunction "F0_3") (pintype "open_collector"))
      (node (ref "E12") (pin "5") (pinfunction "I1_5") (pintype "input"))
      (node (ref "EDGE$") (pin "BV1") (pinfunction "1_BV1") (pintype "bidirectional"))
    )
    (net (code "38") (name "DATA08") (class "Default")
      (node (ref "E07") (pin "4") (pinfunction "I0_4") (pintype "input"))
      (node (ref "E15") (pin "12") (pinfunction "F2_12") (pintype "open_collector"))
      (node (ref "EDGE$") (pin "DR1") (pinfunction "1_DR1") (pintype "bidirectional"))
    )
    (net (code "39") (name "DATA09") (class "Default")
      (node (ref "E15") (pin "13") (pinfunction "F3_13") (pintype "open_collector"))
      (node (ref "E17") (pin "7") (pinfunction "I1_7") (pintype "input"))
      (node (ref "EDGE$") (pin "DS1") (pinfunction "1_DS1") (pintype "bidirectional"))
    )
    (net (code "40") (name "DATA10") (class "Default")
      (node (ref "E12") (pin "7") (pinfunction "I1_7") (pintype "input"))
      (node (ref "E15") (pin "4") (pinfunction "F1_4") (pintype "open_collector"))
      (node (ref "EDGE$") (pin "DU1") (pinfunction "1_DU1") (pintype "bidirectional"))
    )
    (net (code "41") (name "DATA11") (class "Default")
      (node (ref "E07") (pin "7") (pinfunction "I1_7") (pintype "input"))
      (node (ref "E15") (pin "3") (pinfunction "F0_3") (pintype "open_collector"))
      (node (ref "EDGE$") (pin "DV1") (pinfunction "1_DV1") (pintype "bidirectional"))
    )
    (net (code "42") (name "DF_COMP_WD") (class "Default")
      (node (ref "E18") (pin "12") (pinfunction "I0_12") (pintype "input"))
      (node (ref "E18") (pin "5") (pinfunction "I0_5") (pintype "input"))
      (node (ref "E18") (pin "9") (pinfunction "I1_9") (pintype "input"))
      (node (ref "E22") (pin "13") (pinfunction "I1_13") (pintype "input"))
      (node (ref "E22") (pin "3") (pinfunction "O_3") (pintype "output"))
    )
    (net (code "43") (name "DF_DB00") (class "Default")
      (node (ref "E16") (pin "14") (pinfunction "I3_14") (pintype "input"))
      (node (ref "E17") (pin "14") (pinfunction "O_14") (pintype "output"))
      (node (ref "E34") (pin "12") (pinfunction "D_12") (pintype "input"))
      (node (ref "E42") (pin "9") (pinfunction "I1_9") (pintype "input"))
    )
    (net (code "44") (name "DF_DB01") (class "Default")
      (node (ref "E11") (pin "14") (pinfunction "I3_14") (pintype "input"))
      (node (ref "E12") (pin "14") (pinfunction "O_14") (pintype "output"))
      (node (ref "E18") (pin "2") (pinfunction "I1_2") (pintype "input"))
      (node (ref "E34") (pin "2") (pinfunction "D_2") (pintype "input"))
    )
    (net (code "45") (name "DF_DB02") (class "Default")
      (node (ref "E06") (pin "14") (pinfunction "I3_14") (pintype "input"))
      (node (ref "E07") (pin "14") (pinfunction "O_14") (pintype "output"))
      (node (ref "E30") (pin "2") (pinfunction "D_2") (pintype "input"))
      (node (ref "E42") (pin "13") (pinfunction "I1_13") (pintype "input"))
    )
    (net (code "46") (name "DF_DB03") (class "Default")
      (node (ref "E16") (pin "15") (pinfunction "I2_15") (pintype "input"))
      (node (ref "E17") (pin "13") (pinfunction "O_13") (pintype "output"))
      (node (ref "E30") (pin "12") (pinfunction "D_12") (pintype "input"))
    )
    (net (code "47") (name "DF_SEL_ER") (class "Default")
      (node (ref "E32") (pin "12") (pinfunction "O_12") (pintype "output"))
      (node (ref "E37") (pin "6") (pinfunction "I1_6") (pintype "input"))
    )
    (net (code "48") (name "DF_TIME_ER") (class "Default")
      (node (ref "E27") (pin "13") (pinfunction "I2_13") (pintype "input"))
      (node (ref "E35") (pin "6") (pinfunction "O_6") (pintype "output"))
      (node (ref "E37") (pin "5") (pinfunction "I0_5") (pintype "input"))
      (node (ref "E41") (pin "2") (pinfunction "I0_2") (pintype "input"))
    )
    (net (code "49") (name "F{slash}~{R}") (class "Default")
      (node (ref "E39") (pin "8") (pinfunction "O_8") (pintype "open_collector"))
      (node (ref "J1") (pin "TT") (pinfunction "38_TT") (pintype "bidirectional"))
    )
    (net (code "50") (name "GND") (class "Default")
      (node (ref "C1") (pin "2") (pinfunction "2_2") (pintype "passive"))
      (node (ref "C10") (pin "2") (pinfunction "2_2") (pintype "passive"))
      (node (ref "C11") (pin "2") (pinfunction "2_2") (pintype "passive"))
      (node (ref "C12") (pin "2") (pinfunction "2_2") (pintype "passive"))
      (node (ref "C13") (pin "2") (pinfunction "2_2") (pintype "passive"))
      (node (ref "C14") (pin "2") (pinfunction "2_2") (pintype "passive"))
      (node (ref "C15") (pin "2") (pinfunction "2_2") (pintype "passive"))
      (node (ref "C16") (pin "2") (pinfunction "2_2") (pintype "passive"))
      (node (ref "C17") (pin "2") (pinfunction "2_2") (pintype "passive"))
      (node (ref "C18") (pin "2") (pinfunction "2_2") (pintype "passive"))
      (node (ref "C19") (pin "2") (pinfunction "2_2") (pintype "passive"))
      (node (ref "C2") (pin "2") (pinfunction "2_2") (pintype "passive"))
      (node (ref "C20") (pin "2") (pinfunction "2_2") (pintype "passive"))
      (node (ref "C21") (pin "2") (pinfunction "2_2") (pintype "passive"))
      (node (ref "C22") (pin "2") (pinfunction "2_2") (pintype "passive"))
      (node (ref "C23") (pin "2") (pinfunction "2_2") (pintype "passive"))
      (node (ref "C24") (pin "2") (pinfunction "2_2") (pintype "passive"))
      (node (ref "C25") (pin "2") (pinfunction "2_2") (pintype "passive"))
      (node (ref "C26") (pin "2") (pinfunction "2_2") (pintype "passive"))
      (node (ref "C27") (pin "2") (pinfunction "2_2") (pintype "passive"))
      (node (ref "C28") (pin "2") (pinfunction "2_2") (pintype "passive"))
      (node (ref "C29") (pin "2") (pinfunction "2_2") (pintype "passive"))
      (node (ref "C3") (pin "2") (pinfunction "2_2") (pintype "passive"))
      (node (ref "C30") (pin "2") (pinfunction "2_2") (pintype "passive"))
      (node (ref "C31") (pin "2") (pinfunction "2_2") (pintype "passive"))
      (node (ref "C32") (pin "2") (pinfunction "2_2") (pintype "passive"))
      (node (ref "C33") (pin "2") (pinfunction "2_2") (pintype "passive"))
      (node (ref "C34") (pin "-") (pinfunction "-_-") (pintype "passive"))
      (node (ref "C35") (pin "-") (pinfunction "-_-") (pintype "passive"))
      (node (ref "C4") (pin "2") (pinfunction "2_2") (pintype "passive"))
      (node (ref "C40") (pin "2") (pinfunction "2_2") (pintype "passive"))
      (node (ref "C41") (pin "1") (pinfunction "1_1") (pintype "passive"))
      (node (ref "C42") (pin "1") (pinfunction "1_1") (pintype "passive"))
      (node (ref "C43") (pin "2") (pinfunction "2_2") (pintype "passive"))
      (node (ref "C44") (pin "1") (pinfunction "1_1") (pintype "passive"))
      (node (ref "C45") (pin "2") (pinfunction "2_2") (pintype "passive"))
      (node (ref "C46") (pin "-") (pinfunction "-_-") (pintype "passive"))
      (node (ref "C47") (pin "2") (pinfunction "2_2") (pintype "passive"))
      (node (ref "C48") (pin "1") (pinfunction "1_1") (pintype "passive"))
      (node (ref "C5") (pin "2") (pinfunction "2_2") (pintype "passive"))
      (node (ref "C6") (pin "2") (pinfunction "2_2") (pintype "passive"))
      (node (ref "C7") (pin "2") (pinfunction "2_2") (pintype "passive"))
      (node (ref "C8") (pin "2") (pinfunction "2_2") (pintype "passive"))
      (node (ref "C9") (pin "2") (pinfunction "2_2") (pintype "passive"))
      (node (ref "D2") (pin "A") (pinfunction "A_A") (pintype "passive"))
      (node (ref "E04") (pin "1") (pinfunction "A_1") (pintype "input"))
      (node (ref "E08") (pin "1") (pinfunction "A_1") (pintype "input"))
      (node (ref "E08") (pin "9") (pinfunction "A_9") (pintype "input"))
      (node (ref "E20") (pin "10") (pinfunction "I1_10") (pintype "input"))
      (node (ref "E20") (pin "12") (pinfunction "I1_12") (pintype "input"))
      (node (ref "E25") (pin "7") (pinfunction "7_7") (pintype "passive"))
      (node (ref "E28") (pin "10") (pinfunction "I1_10") (pintype "input"))
      (node (ref "E28") (pin "4") (pinfunction "I0_4") (pintype "input"))
      (node (ref "E28") (pin "7") (pinfunction "I1_7") (pintype "input"))
      (node (ref "EDGE$") (pin "AC2") (pinfunction "1_AC2") (pintype "bidirectional"))
      (node (ref "EDGE$") (pin "AF1") (pinfunction "1_AF1") (pintype "bidirectional"))
      (node (ref "EDGE$") (pin "AF2") (pinfunction "1_AF2") (pintype "bidirectional"))
      (node (ref "EDGE$") (pin "AN1") (pinfunction "1_AN1") (pintype "bidirectional"))
      (node (ref "EDGE$") (pin "AN2") (pinfunction "1_AN2") (pintype "bidirectional"))
      (node (ref "EDGE$") (pin "AT1") (pinfunction "1_AT1") (pintype "bidirectional"))
      (node (ref "EDGE$") (pin "AT2") (pinfunction "1_AT2") (pintype "bidirectional"))
      (node (ref "EDGE$") (pin "BC1") (pinfunction "1_BC1") (pintype "bidirectional"))
      (node (ref "EDGE$") (pin "BC2") (pinfunction "1_BC2") (pintype "bidirectional"))
      (node (ref "EDGE$") (pin "BF1") (pinfunction "1_BF1") (pintype "bidirectional"))
      (node (ref "EDGE$") (pin "BF2") (pinfunction "1_BF2") (pintype "bidirectional"))
      (node (ref "EDGE$") (pin "BN2") (pinfunction "1_BN2") (pintype "bidirectional"))
      (node (ref "EDGE$") (pin "BT1") (pinfunction "1_BT1") (pintype "bidirectional"))
      (node (ref "EDGE$") (pin "BT2") (pinfunction "1_BT2") (pintype "bidirectional"))
      (node (ref "EDGE$") (pin "CC1") (pinfunction "1_CC1") (pintype "bidirectional"))
      (node (ref "EDGE$") (pin "CC2") (pinfunction "1_CC2") (pintype "bidirectional"))
      (node (ref "EDGE$") (pin "CF1") (pinfunction "1_CF1") (pintype "bidirectional"))
      (node (ref "EDGE$") (pin "CF2") (pinfunction "1_CF2") (pintype "bidirectional"))
      (node (ref "EDGE$") (pin "CN1") (pinfunction "1_CN1") (pintype "bidirectional"))
      (node (ref "EDGE$") (pin "CN2") (pinfunction "1_CN2") (pintype "bidirectional"))
      (node (ref "EDGE$") (pin "CT1") (pinfunction "1_CT1") (pintype "bidirectional"))
      (node (ref "EDGE$") (pin "CT2") (pinfunction "1_CT2") (pintype "bidirectional"))
      (node (ref "EDGE$") (pin "DC1") (pinfunction "1_DC1") (pintype "bidirectional"))
      (node (ref "EDGE$") (pin "DC2") (pinfunction "1_DC2") (pintype "bidirectional"))
      (node (ref "EDGE$") (pin "DF1") (pinfunction "1_DF1") (pintype "bidirectional"))
      (node (ref "EDGE$") (pin "DF2") (pinfunction "1_DF2") (pintype "bidirectional"))
      (node (ref "EDGE$") (pin "DN1") (pinfunction "1_DN1") (pintype "bidirectional"))
      (node (ref "EDGE$") (pin "DN2") (pinfunction "1_DN2") (pintype "bidirectional"))
      (node (ref "EDGE$") (pin "DT1") (pinfunction "1_DT1") (pintype "bidirectional"))
      (node (ref "EDGE$") (pin "DT2") (pinfunction "1_DT2") (pintype "bidirectional"))
      (node (ref "J1") (pin "A") (pinfunction "1_A") (pintype "bidirectional"))
      (node (ref "J1") (pin "AA") (pinfunction "23_AA") (pintype "bidirectional"))
      (node (ref "J1") (pin "B") (pinfunction "2_B") (pintype "bidirectional"))
      (node (ref "J1") (pin "C") (pinfunction "3_C") (pintype "bidirectional"))
      (node (ref "J1") (pin "CC") (pinfunction "25_CC") (pintype "bidirectional"))
      (node (ref "J1") (pin "E") (pinfunction "5_E") (pintype "bidirectional"))
      (node (ref "J1") (pin "EE") (pinfunction "27_EE") (pintype "bidirectional"))
      (node (ref "J1") (pin "H") (pinfunction "7_H") (pintype "bidirectional"))
      (node (ref "J1") (pin "HH") (pinfunction "29_HH") (pintype "bidirectional"))
      (node (ref "J1") (pin "K") (pinfunction "9_K") (pintype "bidirectional"))
      (node (ref "J1") (pin "KK") (pinfunction "31_KK") (pintype "bidirectional"))
      (node (ref "J1") (pin "M") (pinfunction "11_M") (pintype "bidirectional"))
      (node (ref "J1") (pin "MM") (pinfunction "33_MM") (pintype "bidirectional"))
      (node (ref "J1") (pin "P") (pinfunction "13_P") (pintype "bidirectional"))
      (node (ref "J1") (pin "PP") (pinfunction "35_PP") (pintype "bidirectional"))
      (node (ref "J1") (pin "S") (pinfunction "15_S") (pintype "bidirectional"))
      (node (ref "J1") (pin "SS") (pinfunction "37_SS") (pintype "bidirectional"))
      (node (ref "J1") (pin "U") (pinfunction "17_U") (pintype "bidirectional"))
      (node (ref "J1") (pin "UU") (pinfunction "39_UU") (pintype "bidirectional"))
      (node (ref "J1") (pin "VV") (pinfunction "40_VV") (pintype "bidirectional"))
      (node (ref "J1") (pin "W") (pinfunction "19_W") (pintype "bidirectional"))
      (node (ref "J1") (pin "Y") (pinfunction "21_Y") (pintype "bidirectional"))
      (node (ref "Q4") (pin "3") (pinfunction "C_3") (pintype "passive"))
      (node (ref "Q5") (pin "3") (pinfunction "C_3") (pintype "passive"))
      (node (ref "R36") (pin "2") (pinfunction "2_2") (pintype "passive"))
      (node (ref "R37") (pin "2") (pinfunction "2_2") (pintype "passive"))
      (node (ref "WTM") (pin "2") (pinfunction "S_2") (pintype "passive"))
    )
    (net (code "51") (name "INITIALIZE") (class "Default")
      (node (ref "E28") (pin "5") (pinfunction "I1_5") (pintype "input"))
      (node (ref "EDGE$") (pin "CR1") (pinfunction "1_CR1") (pintype "bidirectional"))
    )
    (net (code "52") (name "INTERNAL_IO") (class "Default")
      (node (ref "E33") (pin "4") (pinfunction "O_4") (pintype "open_collector"))
      (node (ref "EDGE$") (pin "CL1") (pinfunction "1_CL1") (pintype "bidirectional"))
    )
    (net (code "53") (name "IO_PAUSE") (class "Default")
      (node (ref "E28") (pin "9") (pinfunction "I0_9") (pintype "input"))
      (node (ref "EDGE$") (pin "CD1") (pinfunction "1_CD1") (pintype "bidirectional"))
    )
    (net (code "54") (name "MD03") (class "Default")
      (node (ref "E24") (pin "9") (pinfunction "I3_9") (pintype "input"))
      (node (ref "EDGE$") (pin "AP1") (pinfunction "1_AP1") (pintype "bidirectional"))
    )
    (net (code "55") (name "MD04") (class "Default")
      (node (ref "E24") (pin "4") (pinfunction "I0_4") (pintype "input"))
      (node (ref "EDGE$") (pin "BK1") (pinfunction "1_BK1") (pintype "bidirectional"))
    )
    (net (code "56") (name "MD05") (class "Default")
      (node (ref "E24") (pin "5") (pinfunction "I1_5") (pintype "input"))
      (node (ref "EDGE$") (pin "BL1") (pinfunction "1_BL1") (pintype "bidirectional"))
    )
    (net (code "57") (name "MD06") (class "Default")
      (node (ref "E24") (pin "6") (pinfunction "I2_6") (pintype "input"))
      (node (ref "EDGE$") (pin "BM1") (pinfunction "1_BM1") (pintype "bidirectional"))
    )
    (net (code "58") (name "MD07") (class "Default")
      (node (ref "E20") (pin "5") (pinfunction "I1_5") (pintype "input"))
      (node (ref "EDGE$") (pin "BP1") (pinfunction "1_BP1") (pintype "bidirectional"))
      (node (ref "W2W1") (pin "1") (pinfunction "1_1") (pintype "passive"))
    )
    (net (code "59") (name "MD08") (class "Default")
      (node (ref "E20") (pin "6") (pinfunction "I0_6") (pintype "input"))
      (node (ref "EDGE$") (pin "DK1") (pinfunction "1_DK1") (pintype "bidirectional"))
      (node (ref "W4W3") (pin "1") (pinfunction "1_1") (pintype "passive"))
    )
    (net (code "60") (name "MD09") (class "Default")
      (node (ref "E44") (pin "7") (pinfunction "I1_7") (pintype "input"))
      (node (ref "EDGE$") (pin "DL1") (pinfunction "1_DL1") (pintype "bidirectional"))
    )
    (net (code "61") (name "MD10") (class "Default")
      (node (ref "E44") (pin "9") (pinfunction "I0_9") (pintype "input"))
      (node (ref "EDGE$") (pin "DM1") (pinfunction "1_DM1") (pintype "bidirectional"))
    )
    (net (code "62") (name "MD11") (class "Default")
      (node (ref "E44") (pin "11") (pinfunction "I0_11") (pintype "input"))
      (node (ref "EDGE$") (pin "DP1") (pinfunction "1_DP1") (pintype "bidirectional"))
    )
    (net (code "63") (name "N$36") (class "Default")
      (node (ref "E36") (pin "11") (pinfunction "QD_11") (pintype "output"))
      (node (ref "E37") (pin "3") (pinfunction "I1_3") (pintype "input"))
      (node (ref "E41") (pin "12") (pinfunction "I1_12") (pintype "input"))
    )
    (net (code "64") (name "ND0") (class "Default")
      (node (ref "E39") (pin "12") (pinfunction "O_12") (pintype "open_collector"))
      (node (ref "J1") (pin "FF") (pinfunction "28_FF") (pintype "bidirectional"))
    )
    (net (code "65") (name "ND1") (class "Default")
      (node (ref "E39") (pin "4") (pinfunction "O_4") (pintype "open_collector"))
      (node (ref "J1") (pin "DD") (pinfunction "26_DD") (pintype "bidirectional"))
    )
    (net (code "66") (name "ND2") (class "Default")
      (node (ref "E39") (pin "2") (pinfunction "O_2") (pintype "open_collector"))
      (node (ref "J1") (pin "X") (pinfunction "20_X") (pintype "bidirectional"))
    )
    (net (code "67") (name "Net-(D2-PadC)") (class "Default")
      (node (ref "D2") (pin "C") (pinfunction "C_C") (pintype "passive"))
      (node (ref "D3") (pin "A") (pinfunction "A_A") (pintype "passive"))
    )
    (net (code "68") (name "Net-(D4-PadC)") (class "Default")
      (node (ref "D4") (pin "C") (pinfunction "C_C") (pintype "passive"))
      (node (ref "D6") (pin "A") (pinfunction "A_A") (pintype "passive"))
    )
    (net (code "69") (name "Net-(D7-PadC)") (class "Default")
      (node (ref "D7") (pin "C") (pinfunction "C_C") (pintype "passive"))
      (node (ref "D8") (pin "C") (pinfunction "C_C") (pintype "passive"))
      (node (ref "R39") (pin "2") (pinfunction "2_2") (pintype "passive"))
    )
    (net (code "70") (name "Net-(D10-PadC)") (class "Default")
      (node (ref "D10") (pin "C") (pinfunction "C_C") (pintype "passive"))
      (node (ref "D9") (pin "C") (pinfunction "C_C") (pintype "passive"))
      (node (ref "R40") (pin "2") (pinfunction "2_2") (pintype "passive"))
    )
    (net (code "71") (name "Net-(E01B-I)") (class "Default")
      (node (ref "E01") (pin "3") (pinfunction "I_3") (pintype "input"))
      (node (ref "E33") (pin "2") (pinfunction "I0_2") (pintype "input"))
      (node (ref "E44") (pin "2") (pinfunction "O_2") (pintype "output"))
      (node (ref "E45") (pin "1") (pinfunction "C_1") (pintype "input"))
    )
    (net (code "72") (name "Net-(E01B-O)") (class "Default")
      (node (ref "E01") (pin "4") (pinfunction "O_4") (pintype "output"))
      (node (ref "E01") (pin "5") (pinfunction "I_5") (pintype "input"))
    )
    (net (code "73") (name "Net-(E01C-O)") (class "Default")
      (node (ref "E01") (pin "6") (pinfunction "O_6") (pintype "output"))
      (node (ref "E33") (pin "11") (pinfunction "I0_11") (pintype "input"))
    )
    (net (code "74") (name "Net-(E01F-O)") (class "Default")
      (node (ref "E01") (pin "12") (pinfunction "O_12") (pintype "output"))
      (node (ref "R25") (pin "2") (pinfunction "2_2") (pintype "passive"))
    )
    (net (code "75") (name "Net-(E02A-O)") (class "Default")
      (node (ref "E02") (pin "1") (pinfunction "O_1") (pintype "output"))
      (node (ref "E31") (pin "9") (pinfunction "I_9") (pintype "input"))
    )
    (net (code "76") (name "Net-(E02B-I0)") (class "Default")
      (node (ref "E02") (pin "5") (pinfunction "I0_5") (pintype "input"))
      (node (ref "E03") (pin "6") (pinfunction "~{Q}_6") (pintype "output"))
      (node (ref "E04") (pin "2") (pinfunction "B_2") (pintype "input"))
    )
    (net (code "77") (name "Net-(E02B-O)") (class "Default")
      (node (ref "E02") (pin "4") (pinfunction "O_4") (pintype "output"))
      (node (ref "E03") (pin "12") (pinfunction "D_12") (pintype "input"))
      (node (ref "E03") (pin "13") (pinfunction "CLR_13") (pintype "input"))
    )
    (net (code "78") (name "Net-(E02C-I0)") (class "Default")
      (node (ref "E02") (pin "8") (pinfunction "I0_8") (pintype "input"))
      (node (ref "E38") (pin "12") (pinfunction "I0_12") (pintype "input"))
      (node (ref "E38") (pin "8") (pinfunction "O_8") (pintype "output"))
    )
    (net (code "79") (name "Net-(E02C-O)") (class "Default")
      (node (ref "E02") (pin "10") (pinfunction "O_10") (pintype "output"))
      (node (ref "E46") (pin "8") (pinfunction "I0_8") (pintype "input"))
    )
    (net (code "80") (name "Net-(E02D-O)") (class "Default")
      (node (ref "E02") (pin "13") (pinfunction "O_13") (pintype "output"))
      (node (ref "E09") (pin "2") (pinfunction "D_2") (pintype "input"))
    )
    (net (code "81") (name "Net-(E03A-CLK)") (class "Default")
      (node (ref "E03") (pin "3") (pinfunction "CLK_3") (pintype "input"))
      (node (ref "E26") (pin "5") (pinfunction "I_5") (pintype "input"))
      (node (ref "E30") (pin "11") (pinfunction "CLK_11") (pintype "input"))
      (node (ref "E30") (pin "3") (pinfunction "CLK_3") (pintype "input"))
      (node (ref "E34") (pin "11") (pinfunction "CLK_11") (pintype "input"))
      (node (ref "E34") (pin "3") (pinfunction "CLK_3") (pintype "input"))
      (node (ref "E37") (pin "13") (pinfunction "O_13") (pintype "output"))
    )
    (net (code "82") (name "Net-(E03A-CLR)") (class "Default")
      (node (ref "E03") (pin "1") (pinfunction "CLR_1") (pintype "input"))
      (node (ref "E04") (pin "3") (pinfunction "CLR_3") (pintype "input"))
      (node (ref "R42") (pin "2") (pinfunction "2_2") (pintype "passive"))
    )
    (net (code "83") (name "Net-(E03A-D)") (class "Default")
      (node (ref "E03") (pin "2") (pinfunction "D_2") (pintype "input"))
      (node (ref "E18") (pin "3") (pinfunction "O_3") (pintype "open_collector"))
      (node (ref "E42") (pin "10") (pinfunction "O_10") (pintype "open_collector"))
      (node (ref "E42") (pin "11") (pinfunction "O_11") (pintype "open_collector"))
      (node (ref "R15") (pin "1") (pinfunction "1_1") (pintype "passive"))
    )
    (net (code "84") (name "Net-(E03A-PRE)") (class "Default")
      (node (ref "E03") (pin "4") (pinfunction "PRE_4") (pintype "input"))
      (node (ref "E43") (pin "12") (pinfunction "I1_12") (pintype "input"))
      (node (ref "E44") (pin "3") (pinfunction "O_3") (pintype "output"))
    )
    (net (code "85") (name "Net-(E03B-CLK)") (class "Default")
      (node (ref "E03") (pin "11") (pinfunction "CLK_11") (pintype "input"))
      (node (ref "E04") (pin "4") (pinfunction "~{Q}_4") (pintype "output"))
    )
    (net (code "86") (name "Net-(E04A-C)") (class "Default")
      (node (ref "C36") (pin "-") (pinfunction "-_-") (pintype "passive"))
      (node (ref "E04") (pin "14") (pinfunction "C_14") (pintype "input"))
    )
    (net (code "87") (name "Net-(E04A-R{slash}C)") (class "Default")
      (node (ref "C36") (pin "+") (pinfunction "+_+") (pintype "passive"))
      (node (ref "E04") (pin "15") (pinfunction "R/C_15") (pintype "input"))
      (node (ref "R17") (pin "1") (pinfunction "1_1") (pintype "passive"))
    )
    (net (code "88") (name "Net-(E04B-C)") (class "Default")
      (node (ref "C39") (pin "2") (pinfunction "2_2") (pintype "passive"))
      (node (ref "E04") (pin "6") (pinfunction "C_6") (pintype "input"))
    )
    (net (code "89") (name "Net-(E04B-R{slash}C)") (class "Default")
      (node (ref "C39") (pin "1") (pinfunction "1_1") (pintype "passive"))
      (node (ref "E04") (pin "7") (pinfunction "R/C_7") (pintype "input"))
      (node (ref "R43") (pin "1") (pinfunction "1_1") (pintype "passive"))
    )
    (net (code "90") (name "Net-(E06A-C)") (class "Default")
      (node (ref "E06") (pin "6") (pinfunction "C_6") (pintype "input"))
      (node (ref "E11") (pin "6") (pinfunction "C_6") (pintype "input"))
      (node (ref "E16") (pin "6") (pinfunction "C_6") (pintype "input"))
      (node (ref "E26") (pin "8") (pinfunction "O_8") (pintype "output"))
    )
    (net (code "91") (name "Net-(E06A-I0)") (class "Default")
      (node (ref "E06") (pin "3") (pinfunction "I0_3") (pintype "input"))
      (node (ref "E07") (pin "2") (pinfunction "O_2") (pintype "output"))
    )
    (net (code "92") (name "Net-(E06A-I1)") (class "Default")
      (node (ref "E06") (pin "2") (pinfunction "I1_2") (pintype "input"))
      (node (ref "E07") (pin "3") (pinfunction "O_3") (pintype "output"))
    )
    (net (code "93") (name "Net-(E06A-I2)") (class "Default")
      (node (ref "E06") (pin "15") (pinfunction "I2_15") (pintype "input"))
      (node (ref "E07") (pin "13") (pinfunction "O_13") (pintype "output"))
    )
    (net (code "94") (name "Net-(E06A-L)") (class "Default")
      (node (ref "E06") (pin "1") (pinfunction "R_1") (pintype "input"))
      (node (ref "E06") (pin "10") (pinfunction "L_10") (pintype "input"))
      (node (ref "E11") (pin "1") (pinfunction "R_1") (pintype "input"))
      (node (ref "E11") (pin "10") (pinfunction "L_10") (pintype "input"))
      (node (ref "E16") (pin "1") (pinfunction "R_1") (pintype "input"))
      (node (ref "E16") (pin "10") (pinfunction "L_10") (pintype "input"))
      (node (ref "R3") (pin "1") (pinfunction "1_1") (pintype "passive"))
    )
    (net (code "95") (name "Net-(E08A-B)") (class "Default")
      (node (ref "E08") (pin "2") (pinfunction "B_2") (pintype "input"))
      (node (ref "E08") (pin "5") (pinfunction "Q_5") (pintype "output"))
    )
    (net (code "96") (name "Net-(E08A-C)") (class "Default")
      (node (ref "C38") (pin "2") (pinfunction "2_2") (pintype "passive"))
      (node (ref "E08") (pin "14") (pinfunction "C_14") (pintype "input"))
    )
    (net (code "97") (name "Net-(E08A-CLR)") (class "Default")
      (node (ref "E08") (pin "11") (pinfunction "CLR_11") (pintype "input"))
      (node (ref "E08") (pin "3") (pinfunction "CLR_3") (pintype "input"))
      (node (ref "E09") (pin "10") (pinfunction "PRE_10") (pintype "input"))
      (node (ref "E09") (pin "13") (pinfunction "CLR_13") (pintype "input"))
      (node (ref "E09") (pin "4") (pinfunction "PRE_4") (pintype "input"))
      (node (ref "E14") (pin "1") (pinfunction "CLR_1") (pintype "input"))
      (node (ref "E14") (pin "10") (pinfunction "PRE_10") (pintype "input"))
      (node (ref "E14") (pin "13") (pinfunction "CLR_13") (pintype "input"))
      (node (ref "E14") (pin "4") (pinfunction "PRE_4") (pintype "input"))
      (node (ref "R22") (pin "2") (pinfunction "2_2") (pintype "passive"))
    )
    (net (code "98") (name "Net-(E08A-R{slash}C)") (class "Default")
      (node (ref "C38") (pin "1") (pinfunction "1_1") (pintype "passive"))
      (node (ref "E08") (pin "15") (pinfunction "R/C_15") (pintype "input"))
      (node (ref "R24") (pin "1") (pinfunction "1_1") (pintype "passive"))
    )
    (net (code "99") (name "Net-(E08B-C)") (class "Default")
      (node (ref "C37") (pin "2") (pinfunction "2_2") (pintype "passive"))
      (node (ref "E08") (pin "6") (pinfunction "C_6") (pintype "input"))
    )
    (net (code "100") (name "Net-(E08B-R{slash}C)") (class "Default")
      (node (ref "C37") (pin "1") (pinfunction "1_1") (pintype "passive"))
      (node (ref "E08") (pin "7") (pinfunction "R/C_7") (pintype "input"))
      (node (ref "R23") (pin "1") (pinfunction "1_1") (pintype "passive"))
    )
    (net (code "101") (name "Net-(E08B-~{Q})") (class "Default")
      (node (ref "E08") (pin "12") (pinfunction "~{Q}_12") (pintype "output"))
      (node (ref "E09") (pin "11") (pinfunction "CLK_11") (pintype "input"))
      (node (ref "E09") (pin "3") (pinfunction "CLK_3") (pintype "input"))
      (node (ref "E19") (pin "9") (pinfunction "I0_9") (pintype "input"))
    )
    (net (code "102") (name "Net-(E09A-Q)") (class "Default")
      (node (ref "E09") (pin "5") (pinfunction "Q_5") (pintype "output"))
      (node (ref "E23") (pin "9") (pinfunction "I0_9") (pintype "input"))
      (node (ref "E27") (pin "9") (pinfunction "I0_9") (pintype "input"))
    )
    (net (code "103") (name "Net-(E09B-D)") (class "Default")
      (node (ref "E09") (pin "12") (pinfunction "D_12") (pintype "input"))
      (node (ref "E09") (pin "8") (pinfunction "~{Q}_8") (pintype "output"))
      (node (ref "E23") (pin "11") (pinfunction "I2_11") (pintype "input"))
    )
    (net (code "104") (name "Net-(E10A-B3)") (class "Default")
      (node (ref "E10") (pin "14") (pinfunction "B3_14") (pintype "input"))
      (node (ref "E37") (pin "4") (pinfunction "O_4") (pintype "output"))
    )
    (net (code "105") (name "Net-(E11A-I0)") (class "Default")
      (node (ref "E11") (pin "3") (pinfunction "I0_3") (pintype "input"))
      (node (ref "E12") (pin "2") (pinfunction "O_2") (pintype "output"))
    )
    (net (code "106") (name "Net-(E11A-I1)") (class "Default")
      (node (ref "E11") (pin "2") (pinfunction "I1_2") (pintype "input"))
      (node (ref "E12") (pin "3") (pinfunction "O_3") (pintype "output"))
    )
    (net (code "107") (name "Net-(E11A-I2)") (class "Default")
      (node (ref "E11") (pin "15") (pinfunction "I2_15") (pintype "input"))
      (node (ref "E12") (pin "13") (pinfunction "O_13") (pintype "output"))
    )
    (net (code "108") (name "Net-(E13A-C12)") (class "Default")
      (node (ref "E13") (pin "13") (pinfunction "C12_13") (pintype "input"))
      (node (ref "E13") (pin "4") (pinfunction "C34_4") (pintype "input"))
      (node (ref "E31") (pin "12") (pinfunction "O_12") (pintype "output"))
    )
    (net (code "109") (name "Net-(E13A-~{Q1})") (class "Default")
      (node (ref "E13") (pin "1") (pinfunction "~{Q1}_1") (pintype "output"))
      (node (ref "E18") (pin "13") (pinfunction "I1_13") (pintype "input"))
    )
    (net (code "110") (name "Net-(E13A-~{Q3})") (class "Default")
      (node (ref "E13") (pin "11") (pinfunction "~{Q3}_11") (pintype "output"))
      (node (ref "E18") (pin "6") (pinfunction "I1_6") (pintype "input"))
    )
    (net (code "111") (name "Net-(E13A-~{Q4})") (class "Default")
      (node (ref "E13") (pin "8") (pinfunction "~{Q4}_8") (pintype "output"))
      (node (ref "E18") (pin "8") (pinfunction "I0_8") (pintype "input"))
    )
    (net (code "112") (name "Net-(E14A-D)") (class "Default")
      (node (ref "E14") (pin "2") (pinfunction "D_2") (pintype "input"))
      (node (ref "E14") (pin "8") (pinfunction "~{Q}_8") (pintype "output"))
      (node (ref "E23") (pin "3") (pinfunction "I0_3") (pintype "input"))
      (node (ref "E39") (pin "5") (pinfunction "I_5") (pintype "input"))
    )
    (net (code "113") (name "Net-(E16A-I0)") (class "Default")
      (node (ref "E16") (pin "3") (pinfunction "I0_3") (pintype "input"))
      (node (ref "E17") (pin "2") (pinfunction "O_2") (pintype "output"))
    )
    (net (code "114") (name "Net-(E16A-I1)") (class "Default")
      (node (ref "E16") (pin "2") (pinfunction "I1_2") (pintype "input"))
      (node (ref "E17") (pin "3") (pinfunction "O_3") (pintype "output"))
    )
    (net (code "115") (name "Net-(E18B-O)") (class "Default")
      (node (ref "E18") (pin "4") (pinfunction "O_4") (pintype "open_collector"))
      (node (ref "E39") (pin "13") (pinfunction "I_13") (pintype "input"))
      (node (ref "R10") (pin "1") (pinfunction "1_1") (pintype "passive"))
    )
    (net (code "116") (name "Net-(E18C-O)") (class "Default")
      (node (ref "E18") (pin "10") (pinfunction "O_10") (pintype "open_collector"))
      (node (ref "E39") (pin "3") (pinfunction "I_3") (pintype "input"))
      (node (ref "R9") (pin "1") (pinfunction "1_1") (pintype "passive"))
    )
    (net (code "117") (name "Net-(E18D-O)") (class "Default")
      (node (ref "E18") (pin "11") (pinfunction "O_11") (pintype "open_collector"))
      (node (ref "E39") (pin "1") (pinfunction "I_1") (pintype "input"))
      (node (ref "R8") (pin "1") (pinfunction "1_1") (pintype "passive"))
    )
    (net (code "118") (name "Net-(E19A-I0)") (class "Default")
      (node (ref "E19") (pin "1") (pinfunction "I0_1") (pintype "input"))
      (node (ref "E23") (pin "8") (pinfunction "O_8") (pintype "output"))
    )
    (net (code "119") (name "Net-(E19A-I1)") (class "Default")
      (node (ref "E19") (pin "2") (pinfunction "I1_2") (pintype "input"))
      (node (ref "E23") (pin "12") (pinfunction "O_12") (pintype "output"))
    )
    (net (code "120") (name "Net-(E19B-I0)") (class "Default")
      (node (ref "E19") (pin "4") (pinfunction "I0_4") (pintype "input"))
      (node (ref "E27") (pin "8") (pinfunction "O_8") (pintype "output"))
    )
    (net (code "121") (name "Net-(E19B-I1)") (class "Default")
      (node (ref "E19") (pin "5") (pinfunction "I1_5") (pintype "input"))
      (node (ref "E23") (pin "6") (pinfunction "O_6") (pintype "output"))
    )
    (net (code "122") (name "Net-(E19C-I1)") (class "Default")
      (node (ref "E19") (pin "10") (pinfunction "I1_10") (pintype "input"))
      (node (ref "E43") (pin "1") (pinfunction "O_1") (pintype "open_collector"))
      (node (ref "E43") (pin "4") (pinfunction "O_4") (pintype "open_collector"))
      (node (ref "R21") (pin "1") (pinfunction "1_1") (pintype "passive"))
    )
    (net (code "123") (name "Net-(E19D-I0)") (class "Default")
      (node (ref "E19") (pin "12") (pinfunction "I0_12") (pintype "input"))
      (node (ref "E26") (pin "1") (pinfunction "I_1") (pintype "input"))
      (node (ref "E40") (pin "8") (pinfunction "O_8") (pintype "output"))
    )
    (net (code "124") (name "Net-(E19D-O)") (class "Default")
      (node (ref "E19") (pin "11") (pinfunction "O_11") (pintype "output"))
      (node (ref "E30") (pin "13") (pinfunction "CLR_13") (pintype "input"))
    )
    (net (code "125") (name "Net-(E20A-I0)") (class "Default")
      (node (ref "E20") (pin "4") (pinfunction "I0_4") (pintype "input"))
      (node (ref "E20") (pin "7") (pinfunction "I1_7") (pintype "input"))
      (node (ref "E24") (pin "10") (pinfunction "I4_10") (pintype "input"))
      (node (ref "E28") (pin "14") (pinfunction "O_14") (pintype "output"))
    )
    (net (code "126") (name "Net-(E20A-O)") (class "Default")
      (node (ref "E20") (pin "3") (pinfunction "O_3") (pintype "output"))
      (node (ref "W2W1") (pin "3") (pinfunction "3_3") (pintype "passive"))
    )
    (net (code "127") (name "Net-(E20B-O)") (class "Default")
      (node (ref "E20") (pin "2") (pinfunction "O_2") (pintype "output"))
      (node (ref "W4W3") (pin "3") (pinfunction "3_3") (pintype "passive"))
    )
    (net (code "128") (name "Net-(E21A-C)") (class "Default")
      (node (ref "E21") (pin "6") (pinfunction "C_6") (pintype "input"))
      (node (ref "E22") (pin "6") (pinfunction "O_6") (pintype "output"))
      (node (ref "E29") (pin "6") (pinfunction "C_6") (pintype "input"))
    )
    (net (code "129") (name "Net-(E21A-I0)") (class "Default")
      (node (ref "E21") (pin "1") (pinfunction "R_1") (pintype "input"))
      (node (ref "E21") (pin "10") (pinfunction "L_10") (pintype "input"))
      (node (ref "E21") (pin "14") (pinfunction "I3_14") (pintype "input"))
      (node (ref "E21") (pin "15") (pinfunction "I2_15") (pintype "input"))
      (node (ref "E21") (pin "2") (pinfunction "I1_2") (pintype "input"))
      (node (ref "E21") (pin "3") (pinfunction "I0_3") (pintype "input"))
      (node (ref "E29") (pin "1") (pinfunction "R_1") (pintype "input"))
      (node (ref "E29") (pin "10") (pinfunction "L_10") (pintype "input"))
      (node (ref "E29") (pin "14") (pinfunction "I3_14") (pintype "input"))
      (node (ref "E29") (pin "15") (pinfunction "I2_15") (pintype "input"))
      (node (ref "E29") (pin "2") (pinfunction "I1_2") (pintype "input"))
      (node (ref "E29") (pin "3") (pinfunction "I0_3") (pintype "input"))
      (node (ref "R2") (pin "1") (pinfunction "1_1") (pintype "passive"))
    )
    (net (code "130") (name "Net-(E22A-I0)") (class "Default")
      (node (ref "E22") (pin "1") (pinfunction "I0_1") (pintype "input"))
      (node (ref "E22") (pin "11") (pinfunction "O_11") (pintype "output"))
    )
    (net (code "131") (name "Net-(E22C-I1)") (class "Default")
      (node (ref "E22") (pin "10") (pinfunction "I1_10") (pintype "input"))
      (node (ref "E31") (pin "8") (pinfunction "O_8") (pintype "output"))
    )
    (net (code "132") (name "Net-(E22C-O)") (class "Default")
      (node (ref "E22") (pin "8") (pinfunction "O_8") (pintype "output"))
      (node (ref "E26") (pin "9") (pinfunction "I_9") (pintype "input"))
    )
    (net (code "133") (name "Net-(E24A-I5)") (class "Default")
      (node (ref "E24") (pin "11") (pinfunction "I5_11") (pintype "input"))
      (node (ref "W2W1") (pin "2") (pinfunction "2_2") (pintype "passive"))
    )
    (net (code "134") (name "Net-(E24A-I6)") (class "Default")
      (node (ref "E24") (pin "12") (pinfunction "I6_12") (pintype "input"))
      (node (ref "W4W3") (pin "2") (pinfunction "2_2") (pintype "passive"))
    )
    (net (code "135") (name "Net-(E24A-O)") (class "Default")
      (node (ref "E24") (pin "3") (pinfunction "O_3") (pintype "output"))
      (node (ref "E26") (pin "11") (pinfunction "I_11") (pintype "input"))
      (node (ref "E33") (pin "5") (pinfunction "I0_5") (pintype "input"))
      (node (ref "E33") (pin "6") (pinfunction "I1_6") (pintype "input"))
    )
    (net (code "136") (name "Net-(E26B-I)") (class "Default")
      (node (ref "E26") (pin "3") (pinfunction "I_3") (pintype "input"))
      (node (ref "E43") (pin "10") (pinfunction "O_10") (pintype "open_collector"))
      (node (ref "E43") (pin "11") (pinfunction "I0_11") (pintype "input"))
      (node (ref "R14") (pin "2") (pinfunction "2_2") (pintype "passive"))
    )
    (net (code "137") (name "Net-(E26B-O)") (class "Default")
      (node (ref "E26") (pin "4") (pinfunction "O_4") (pintype "output"))
      (node (ref "E46") (pin "11") (pinfunction "I0_11") (pintype "input"))
    )
    (net (code "138") (name "Net-(E27B-O)") (class "Default")
      (node (ref "E27") (pin "6") (pinfunction "O_6") (pintype "output"))
      (node (ref "E37") (pin "2") (pinfunction "I0_2") (pintype "input"))
      (node (ref "E38") (pin "1") (pinfunction "I0_1") (pintype "input"))
    )
    (net (code "139") (name "Net-(E30A-CLR)") (class "Default")
      (node (ref "E30") (pin "1") (pinfunction "CLR_1") (pintype "input"))
      (node (ref "E37") (pin "10") (pinfunction "O_10") (pintype "output"))
    )
    (net (code "140") (name "Net-(E30A-PRE)") (class "Default")
      (node (ref "E30") (pin "10") (pinfunction "PRE_10") (pintype "input"))
      (node (ref "E30") (pin "4") (pinfunction "PRE_4") (pintype "input"))
      (node (ref "E34") (pin "10") (pinfunction "PRE_10") (pintype "input"))
      (node (ref "E34") (pin "4") (pinfunction "PRE_4") (pintype "input"))
      (node (ref "R12") (pin "1") (pinfunction "1_1") (pintype "passive"))
    )
    (net (code "141") (name "Net-(E31E-I)") (class "Default")
      (node (ref "E31") (pin "11") (pinfunction "I_11") (pintype "input"))
      (node (ref "E37") (pin "1") (pinfunction "O_1") (pintype "output"))
    )
    (net (code "142") (name "Net-(E31E-O)") (class "Default")
      (node (ref "E31") (pin "10") (pinfunction "O_10") (pintype "output"))
      (node (ref "E35") (pin "11") (pinfunction "I2_11") (pintype "input"))
      (node (ref "E35") (pin "13") (pinfunction "I2_13") (pintype "input"))
    )
    (net (code "143") (name "Net-(E32A-O)") (class "Default")
      (node (ref "E32") (pin "2") (pinfunction "O_2") (pintype "output"))
      (node (ref "E41") (pin "11") (pinfunction "I0_11") (pintype "input"))
    )
    (net (code "144") (name "Net-(E32B-O)") (class "Default")
      (node (ref "E32") (pin "4") (pinfunction "O_4") (pintype "output"))
      (node (ref "E41") (pin "9") (pinfunction "I1_9") (pintype "input"))
    )
    (net (code "145") (name "Net-(E32C-O)") (class "Default")
      (node (ref "E32") (pin "6") (pinfunction "O_6") (pintype "output"))
      (node (ref "E41") (pin "3") (pinfunction "I1_3") (pintype "input"))
    )
    (net (code "146") (name "Net-(E32D-I)") (class "Default")
      (node (ref "E32") (pin "9") (pinfunction "I_9") (pintype "input"))
      (node (ref "Q1") (pin "3") (pinfunction "C_3") (pintype "passive"))
      (node (ref "R27") (pin "1") (pinfunction "1_1") (pintype "passive"))
    )
    (net (code "147") (name "Net-(E33A-I1)") (class "Default")
      (node (ref "E33") (pin "3") (pinfunction "I1_3") (pintype "input"))
      (node (ref "E44") (pin "14") (pinfunction "O_14") (pintype "output"))
      (node (ref "E45") (pin "14") (pinfunction "B_14") (pintype "input"))
    )
    (net (code "148") (name "Net-(E35A-O)") (class "Default")
      (node (ref "E35") (pin "12") (pinfunction "O_12") (pintype "output"))
      (node (ref "E35") (pin "3") (pinfunction "I0_3") (pintype "input"))
    )
    (net (code "149") (name "Net-(E35B-I1)") (class "Default")
      (node (ref "E35") (pin "4") (pinfunction "I1_4") (pintype "input"))
      (node (ref "E35") (pin "8") (pinfunction "O_8") (pintype "output"))
    )
    (net (code "150") (name "Net-(E36A-QA)") (class "Default")
      (node (ref "E36") (pin "12") (pinfunction "QA_12") (pintype "output"))
      (node (ref "E41") (pin "8") (pinfunction "I0_8") (pintype "input"))
    )
    (net (code "151") (name "Net-(E36A-R0(1))") (class "Default")
      (node (ref "E36") (pin "2") (pinfunction "R0(1)_2") (pintype "input"))
      (node (ref "E36") (pin "3") (pinfunction "R0(2)_3") (pintype "input"))
      (node (ref "E38") (pin "6") (pinfunction "O_6") (pintype "output"))
    )
    (net (code "152") (name "Net-(E38A-O)") (class "Default")
      (node (ref "E38") (pin "3") (pinfunction "O_3") (pintype "output"))
      (node (ref "E38") (pin "4") (pinfunction "I0_4") (pintype "input"))
    )
    (net (code "153") (name "Net-(E38C-I1)") (class "Default")
      (node (ref "E38") (pin "10") (pinfunction "I1_10") (pintype "input"))
      (node (ref "E38") (pin "11") (pinfunction "O_11") (pintype "output"))
    )
    (net (code "154") (name "Net-(E42A-O)") (class "Default")
      (node (ref "E42") (pin "3") (pinfunction "O_3") (pintype "open_collector"))
      (node (ref "E43") (pin "5") (pinfunction "I0_5") (pintype "input"))
      (node (ref "R20") (pin "1") (pinfunction "1_1") (pintype "passive"))
    )
    (net (code "155") (name "Net-(E42B-O)") (class "Default")
      (node (ref "E42") (pin "4") (pinfunction "O_4") (pintype "open_collector"))
      (node (ref "E43") (pin "3") (pinfunction "I1_3") (pintype "input"))
      (node (ref "R19") (pin "1") (pinfunction "1_1") (pintype "passive"))
    )
    (net (code "156") (name "Net-(E43C-I1)") (class "Default")
      (node (ref "E43") (pin "13") (pinfunction "O_13") (pintype "open_collector"))
      (node (ref "E43") (pin "9") (pinfunction "I1_9") (pintype "input"))
      (node (ref "R13") (pin "2") (pinfunction "2_2") (pintype "passive"))
    )
    (net (code "157") (name "Net-(E44D-O)") (class "Default")
      (node (ref "E44") (pin "13") (pinfunction "O_13") (pintype "output"))
      (node (ref "E45") (pin "15") (pinfunction "A_15") (pintype "input"))
    )
    (net (code "158") (name "Net-(Q1-B)") (class "Default")
      (node (ref "D1") (pin "C") (pinfunction "C_C") (pintype "passive"))
      (node (ref "Q1") (pin "2") (pinfunction "B_2") (pintype "passive"))
      (node (ref "R48") (pin "2") (pinfunction "2_2") (pintype "passive"))
    )
    (net (code "159") (name "Net-(Q1-E)") (class "Default")
      (node (ref "D5") (pin "C") (pinfunction "C_C") (pintype "passive"))
      (node (ref "Q1") (pin "1") (pinfunction "E_1") (pintype "passive"))
      (node (ref "R41") (pin "2") (pinfunction "2_2") (pintype "passive"))
    )
    (net (code "160") (name "Net-(Q2-E)") (class "Default")
      (node (ref "D8") (pin "A") (pinfunction "A_A") (pintype "passive"))
      (node (ref "Q2") (pin "1") (pinfunction "E_1") (pintype "passive"))
    )
    (net (code "161") (name "Net-(Q3-E)") (class "Default")
      (node (ref "D9") (pin "A") (pinfunction "A_A") (pintype "passive"))
      (node (ref "Q3") (pin "1") (pinfunction "E_1") (pintype "passive"))
    )
    (net (code "162") (name "Net-(Q4-E)") (class "Default")
      (node (ref "D7") (pin "A") (pinfunction "A_A") (pintype "passive"))
      (node (ref "Q4") (pin "1") (pinfunction "E_1") (pintype "passive"))
    )
    (net (code "163") (name "Net-(Q5-E)") (class "Default")
      (node (ref "D10") (pin "A") (pinfunction "A_A") (pintype "passive"))
      (node (ref "Q5") (pin "1") (pinfunction "E_1") (pintype "passive"))
    )
    (net (code "164") (name "Net-(R26-A)") (class "Default")
      (node (ref "R26") (pin "1") (pinfunction "A_1") (pintype "passive"))
      (node (ref "R43") (pin "2") (pinfunction "2_2") (pintype "passive"))
    )
    (net (code "165") (name "RD00") (class "Default")
      (node (ref "E16") (pin "4") (pinfunction "D_4") (pintype "input"))
      (node (ref "J1") (pin "D") (pinfunction "4_D") (pintype "bidirectional"))
      (node (ref "R4") (pin "1") (pinfunction "1_1") (pintype "passive"))
    )
    (net (code "166") (name "RD01") (class "Default")
      (node (ref "E11") (pin "4") (pinfunction "D_4") (pintype "input"))
      (node (ref "J1") (pin "L") (pinfunction "10_L") (pintype "bidirectional"))
      (node (ref "R5") (pin "1") (pinfunction "1_1") (pintype "passive"))
    )
    (net (code "167") (name "RD02") (class "Default")
      (node (ref "E06") (pin "4") (pinfunction "D_4") (pintype "input"))
      (node (ref "J1") (pin "V") (pinfunction "18_V") (pintype "bidirectional"))
      (node (ref "R7") (pin "1") (pinfunction "1_1") (pintype "passive"))
    )
    (net (code "168") (name "RMT") (class "Default")
      (node (ref "E21") (pin "4") (pinfunction "D_4") (pintype "input"))
      (node (ref "J1") (pin "F") (pinfunction "6_F") (pintype "bidirectional"))
      (node (ref "R1") (pin "1") (pinfunction "1_1") (pintype "passive"))
    )
    (net (code "169") (name "RUN") (class "Default")
      (node (ref "E20") (pin "9") (pinfunction "I0_9") (pintype "input"))
      (node (ref "EDGE$") (pin "BU2") (pinfunction "1_BU2") (pintype "bidirectional"))
    )
    (net (code "170") (name "SEL_ECHO") (class "Default")
      (node (ref "J1") (pin "N") (pinfunction "12_N") (pintype "bidirectional"))
      (node (ref "Q2") (pin "2") (pinfunction "B_2") (pintype "passive"))
      (node (ref "Q5") (pin "2") (pinfunction "B_2") (pintype "passive"))
      (node (ref "R30") (pin "2") (pinfunction "2_2") (pintype "passive"))
      (node (ref "R31") (pin "2") (pinfunction "2_2") (pintype "passive"))
      (node (ref "R32") (pin "2") (pinfunction "2_2") (pintype "passive"))
      (node (ref "R33") (pin "2") (pinfunction "2_2") (pintype "passive"))
      (node (ref "R34") (pin "2") (pinfunction "2_2") (pintype "passive"))
    )
    (net (code "171") (name "SR00") (class "Default")
      (node (ref "E05") (pin "10") (pinfunction "A2_10") (pintype "input"))
      (node (ref "E13") (pin "6") (pinfunction "D3_6") (pintype "input"))
      (node (ref "E16") (pin "11") (pinfunction "Q3_11") (pintype "output"))
    )
    (net (code "172") (name "SR01") (class "Default")
      (node (ref "E05") (pin "15") (pinfunction "A3_15") (pintype "input"))
      (node (ref "E11") (pin "11") (pinfunction "Q3_11") (pintype "output"))
      (node (ref "E13") (pin "7") (pinfunction "D4_7") (pintype "input"))
    )
    (net (code "173") (name "SR02") (class "Default")
      (node (ref "E05") (pin "6") (pinfunction "A1_6") (pintype "input"))
      (node (ref "E06") (pin "11") (pinfunction "Q3_11") (pintype "output"))
      (node (ref "E13") (pin "2") (pinfunction "D1_2") (pintype "input"))
    )
    (net (code "174") (name "SR03") (class "Default")
      (node (ref "E05") (pin "1") (pinfunction "A0_1") (pintype "input"))
      (node (ref "E16") (pin "9") (pinfunction "Q2_9") (pintype "output"))
    )
    (net (code "175") (name "SR04") (class "Default")
      (node (ref "E10") (pin "10") (pinfunction "A2_10") (pintype "input"))
      (node (ref "E11") (pin "9") (pinfunction "Q2_9") (pintype "output"))
    )
    (net (code "176") (name "SR05") (class "Default")
      (node (ref "E06") (pin "9") (pinfunction "Q2_9") (pintype "output"))
      (node (ref "E10") (pin "15") (pinfunction "A3_15") (pintype "input"))
    )
    (net (code "177") (name "SR06") (class "Default")
      (node (ref "E10") (pin "6") (pinfunction "A1_6") (pintype "input"))
      (node (ref "E16") (pin "7") (pinfunction "Q1_7") (pintype "output"))
    )
    (net (code "178") (name "SR07") (class "Default")
      (node (ref "E10") (pin "1") (pinfunction "A0_1") (pintype "input"))
      (node (ref "E11") (pin "7") (pinfunction "Q1_7") (pintype "output"))
    )
    (net (code "179") (name "SR08") (class "Default")
      (node (ref "E06") (pin "7") (pinfunction "Q1_7") (pintype "output"))
      (node (ref "E15") (pin "10") (pinfunction "A2_10") (pintype "input"))
    )
    (net (code "180") (name "SR09") (class "Default")
      (node (ref "E15") (pin "15") (pinfunction "A3_15") (pintype "input"))
      (node (ref "E16") (pin "5") (pinfunction "Q0_5") (pintype "output"))
    )
    (net (code "181") (name "SR10") (class "Default")
      (node (ref "E11") (pin "5") (pinfunction "Q0_5") (pintype "output"))
      (node (ref "E15") (pin "6") (pinfunction "A1_6") (pintype "input"))
    )
    (net (code "182") (name "SR11") (class "Default")
      (node (ref "E06") (pin "5") (pinfunction "Q0_5") (pintype "output"))
      (node (ref "E15") (pin "1") (pinfunction "A0_1") (pintype "input"))
    )
    (net (code "183") (name "SYNC") (class "Default")
      (node (ref "E09") (pin "9") (pinfunction "Q_9") (pintype "output"))
      (node (ref "E27") (pin "11") (pinfunction "I2_11") (pintype "input"))
      (node (ref "E42") (pin "2") (pinfunction "I1_2") (pintype "input"))
      (node (ref "E42") (pin "5") (pinfunction "I0_5") (pintype "input"))
    )
    (net (code "184") (name "S{slash}~{G}") (class "Default")
      (node (ref "E46") (pin "13") (pinfunction "O_13") (pintype "open_collector"))
      (node (ref "J1") (pin "JJ") (pinfunction "30_JJ") (pintype "bidirectional"))
    )
    (net (code "185") (name "TP3") (class "Default")
      (node (ref "E20") (pin "11") (pinfunction "I0_11") (pintype "input"))
      (node (ref "EDGE$") (pin "CH2") (pinfunction "1_CH2") (pintype "bidirectional"))
    )
    (net (code "186") (name "TP4") (class "Default")
      (node (ref "E44") (pin "5") (pinfunction "I1_5") (pintype "input"))
      (node (ref "EDGE$") (pin "CJ2") (pinfunction "1_CJ2") (pintype "bidirectional"))
    )
    (net (code "187") (name "TPG0") (class "Default")
      (node (ref "E14") (pin "9") (pinfunction "Q_9") (pintype "output"))
      (node (ref "E23") (pin "13") (pinfunction "I2_13") (pintype "input"))
    )
    (net (code "188") (name "T{slash}M_ENABLE") (class "Default")
      (node (ref "E46") (pin "4") (pinfunction "O_4") (pintype "open_collector"))
      (node (ref "J1") (pin "NN") (pinfunction "34_NN") (pintype "bidirectional"))
    )
    (net (code "189") (name "UNITH") (class "Default")
      (node (ref "E39") (pin "10") (pinfunction "O_10") (pintype "open_collector"))
      (node (ref "J1") (pin "LL") (pinfunction "32_LL") (pintype "bidirectional"))
    )
    (net (code "190") (name "VCC") (class "Default")
      (node (ref "C1") (pin "1") (pinfunction "1_1") (pintype "passive"))
      (node (ref "C10") (pin "1") (pinfunction "1_1") (pintype "passive"))
      (node (ref "C11") (pin "1") (pinfunction "1_1") (pintype "passive"))
      (node (ref "C12") (pin "1") (pinfunction "1_1") (pintype "passive"))
      (node (ref "C13") (pin "1") (pinfunction "1_1") (pintype "passive"))
      (node (ref "C14") (pin "1") (pinfunction "1_1") (pintype "passive"))
      (node (ref "C15") (pin "1") (pinfunction "1_1") (pintype "passive"))
      (node (ref "C16") (pin "1") (pinfunction "1_1") (pintype "passive"))
      (node (ref "C17") (pin "1") (pinfunction "1_1") (pintype "passive"))
      (node (ref "C18") (pin "1") (pinfunction "1_1") (pintype "passive"))
      (node (ref "C19") (pin "1") (pinfunction "1_1") (pintype "passive"))
      (node (ref "C2") (pin "1") (pinfunction "1_1") (pintype "passive"))
      (node (ref "C20") (pin "1") (pinfunction "1_1") (pintype "passive"))
      (node (ref "C21") (pin "1") (pinfunction "1_1") (pintype "passive"))
      (node (ref "C22") (pin "1") (pinfunction "1_1") (pintype "passive"))
      (node (ref "C23") (pin "1") (pinfunction "1_1") (pintype "passive"))
      (node (ref "C24") (pin "1") (pinfunction "1_1") (pintype "passive"))
      (node (ref "C25") (pin "1") (pinfunction "1_1") (pintype "passive"))
      (node (ref "C26") (pin "1") (pinfunction "1_1") (pintype "passive"))
      (node (ref "C27") (pin "1") (pinfunction "1_1") (pintype "passive"))
      (node (ref "C28") (pin "1") (pinfunction "1_1") (pintype "passive"))
      (node (ref "C29") (pin "1") (pinfunction "1_1") (pintype "passive"))
      (node (ref "C3") (pin "1") (pinfunction "1_1") (pintype "passive"))
      (node (ref "C30") (pin "1") (pinfunction "1_1") (pintype "passive"))
      (node (ref "C31") (pin "1") (pinfunction "1_1") (pintype "passive"))
      (node (ref "C32") (pin "1") (pinfunction "1_1") (pintype "passive"))
      (node (ref "C33") (pin "1") (pinfunction "1_1") (pintype "passive"))
      (node (ref "C34") (pin "+") (pinfunction "+_+") (pintype "passive"))
      (node (ref "C35") (pin "+") (pinfunction "+_+") (pintype "passive"))
      (node (ref "C4") (pin "1") (pinfunction "1_1") (pintype "passive"))
      (node (ref "C43") (pin "1") (pinfunction "1_1") (pintype "passive"))
      (node (ref "C45") (pin "1") (pinfunction "1_1") (pintype "passive"))
      (node (ref "C46") (pin "+") (pinfunction "+_+") (pintype "passive"))
      (node (ref "C5") (pin "1") (pinfunction "1_1") (pintype "passive"))
      (node (ref "C6") (pin "1") (pinfunction "1_1") (pintype "passive"))
      (node (ref "C7") (pin "1") (pinfunction "1_1") (pintype "passive"))
      (node (ref "C8") (pin "1") (pinfunction "1_1") (pintype "passive"))
      (node (ref "C9") (pin "1") (pinfunction "1_1") (pintype "passive"))
      (node (ref "E25") (pin "14") (pinfunction "14_14") (pintype "passive"))
      (node (ref "EDGE$") (pin "AA2") (pinfunction "1_AA2") (pintype "bidirectional"))
      (node (ref "EDGE$") (pin "BA2") (pinfunction "1_BA2") (pintype "bidirectional"))
      (node (ref "EDGE$") (pin "CA2") (pinfunction "1_CA2") (pintype "bidirectional"))
      (node (ref "R1") (pin "2") (pinfunction "2_2") (pintype "passive"))
      (node (ref "R10") (pin "2") (pinfunction "2_2") (pintype "passive"))
      (node (ref "R11") (pin "2") (pinfunction "2_2") (pintype "passive"))
      (node (ref "R12") (pin "2") (pinfunction "2_2") (pintype "passive"))
      (node (ref "R13") (pin "1") (pinfunction "1_1") (pintype "passive"))
      (node (ref "R14") (pin "1") (pinfunction "1_1") (pintype "passive"))
      (node (ref "R15") (pin "2") (pinfunction "2_2") (pintype "passive"))
      (node (ref "R16") (pin "2") (pinfunction "2_2") (pintype "passive"))
      (node (ref "R17") (pin "2") (pinfunction "2_2") (pintype "passive"))
      (node (ref "R18") (pin "2") (pinfunction "2_2") (pintype "passive"))
      (node (ref "R19") (pin "2") (pinfunction "2_2") (pintype "passive"))
      (node (ref "R2") (pin "2") (pinfunction "2_2") (pintype "passive"))
      (node (ref "R20") (pin "2") (pinfunction "2_2") (pintype "passive"))
      (node (ref "R21") (pin "2") (pinfunction "2_2") (pintype "passive"))
      (node (ref "R22") (pin "1") (pinfunction "1_1") (pintype "passive"))
      (node (ref "R23") (pin "2") (pinfunction "2_2") (pintype "passive"))
      (node (ref "R24") (pin "2") (pinfunction "2_2") (pintype "passive"))
      (node (ref "R26") (pin "2") (pinfunction "S_2") (pintype "passive"))
      (node (ref "R26") (pin "3") (pinfunction "E_3") (pintype "passive"))
      (node (ref "R27") (pin "2") (pinfunction "2_2") (pintype "passive"))
      (node (ref "R3") (pin "2") (pinfunction "2_2") (pintype "passive"))
      (node (ref "R4") (pin "2") (pinfunction "2_2") (pintype "passive"))
      (node (ref "R42") (pin "1") (pinfunction "1_1") (pintype "passive"))
      (node (ref "R5") (pin "2") (pinfunction "2_2") (pintype "passive"))
      (node (ref "R6") (pin "2") (pinfunction "2_2") (pintype "passive"))
      (node (ref "R7") (pin "2") (pinfunction "2_2") (pintype "passive"))
      (node (ref "R8") (pin "2") (pinfunction "2_2") (pintype "passive"))
      (node (ref "R9") (pin "2") (pinfunction "2_2") (pintype "passive"))
    )
    (net (code "191") (name "WD_ENAB") (class "Default")
      (node (ref "E46") (pin "10") (pinfunction "O_10") (pintype "open_collector"))
      (node (ref "J1") (pin "Z") (pinfunction "22_Z") (pintype "bidirectional"))
    )
    (net (code "192") (name "WPT") (class "Default")
      (node (ref "E39") (pin "6") (pinfunction "O_6") (pintype "open_collector"))
      (node (ref "J1") (pin "BB") (pinfunction "24_BB") (pintype "bidirectional"))
    )
    (net (code "193") (name "WRT_ECHO") (class "Default")
      (node (ref "C47") (pin "1") (pinfunction "1_1") (pintype "passive"))
      (node (ref "J1") (pin "T") (pinfunction "16_T") (pintype "bidirectional"))
      (node (ref "R48") (pin "1") (pinfunction "1_1") (pintype "passive"))
    )
    (net (code "194") (name "unconnected-(E04A-Q-Pad13)") (class "Default")
      (node (ref "E04") (pin "13") (pinfunction "Q_13") (pintype "output"))
    )
    (net (code "195") (name "unconnected-(E04B-~{Q}-Pad12)") (class "Default")
      (node (ref "E04") (pin "12") (pinfunction "~{Q}_12") (pintype "output"))
    )
    (net (code "196") (name "unconnected-(E06A-Q4-Pad12)") (class "Default")
      (node (ref "E06") (pin "12") (pinfunction "Q4_12") (pintype "output"))
    )
    (net (code "197") (name "unconnected-(E08A-~{Q}-Pad4)") (class "Default")
      (node (ref "E08") (pin "4") (pinfunction "~{Q}_4") (pintype "output"))
    )
    (net (code "198") (name "unconnected-(E09A-~{Q}-Pad6)") (class "Default")
      (node (ref "E09") (pin "6") (pinfunction "~{Q}_6") (pintype "output"))
    )
    (net (code "199") (name "unconnected-(E11A-Q4-Pad12)") (class "Default")
      (node (ref "E11") (pin "12") (pinfunction "Q4_12") (pintype "output"))
    )
    (net (code "200") (name "unconnected-(E13A-D2-Pad3)") (class "Default")
      (node (ref "E13") (pin "3") (pinfunction "D2_3") (pintype "input"))
    )
    (net (code "201") (name "unconnected-(E13A-Q1-Pad16)") (class "Default")
      (node (ref "E13") (pin "16") (pinfunction "Q1_16") (pintype "output"))
    )
    (net (code "202") (name "unconnected-(E13A-Q2-Pad15)") (class "Default")
      (node (ref "E13") (pin "15") (pinfunction "Q2_15") (pintype "output"))
    )
    (net (code "203") (name "unconnected-(E13A-Q3-Pad10)") (class "Default")
      (node (ref "E13") (pin "10") (pinfunction "Q3_10") (pintype "output"))
    )
    (net (code "204") (name "unconnected-(E13A-Q4-Pad9)") (class "Default")
      (node (ref "E13") (pin "9") (pinfunction "Q4_9") (pintype "output"))
    )
    (net (code "205") (name "unconnected-(E13A-~{Q2}-Pad14)") (class "Default")
      (node (ref "E13") (pin "14") (pinfunction "~{Q2}_14") (pintype "output"))
    )
    (net (code "206") (name "unconnected-(E16A-Q4-Pad12)") (class "Default")
      (node (ref "E16") (pin "12") (pinfunction "Q4_12") (pintype "output"))
    )
    (net (code "207") (name "unconnected-(E21A-Q4-Pad12)") (class "Default")
      (node (ref "E21") (pin "12") (pinfunction "Q4_12") (pintype "output"))
    )
    (net (code "208") (name "unconnected-(E25-Pad1)") (class "Default")
      (node (ref "E25") (pin "1") (pinfunction "1_1") (pintype "passive"))
    )
    (net (code "209") (name "unconnected-(E25-Pad2)") (class "Default")
      (node (ref "E25") (pin "2") (pinfunction "2_2") (pintype "passive"))
    )
    (net (code "210") (name "unconnected-(E25-Pad3)") (class "Default")
      (node (ref "E25") (pin "3") (pinfunction "3_3") (pintype "passive"))
    )
    (net (code "211") (name "unconnected-(E25-Pad4)") (class "Default")
      (node (ref "E25") (pin "4") (pinfunction "4_4") (pintype "passive"))
    )
    (net (code "212") (name "unconnected-(E25-Pad5)") (class "Default")
      (node (ref "E25") (pin "5") (pinfunction "5_5") (pintype "passive"))
    )
    (net (code "213") (name "unconnected-(E25-Pad6)") (class "Default")
      (node (ref "E25") (pin "6") (pinfunction "6_6") (pintype "passive"))
    )
    (net (code "214") (name "unconnected-(E25-Pad8)") (class "Default")
      (node (ref "E25") (pin "8") (pinfunction "8_8") (pintype "passive"))
    )
    (net (code "215") (name "unconnected-(E25-Pad9)") (class "Default")
      (node (ref "E25") (pin "9") (pinfunction "9_9") (pintype "passive"))
    )
    (net (code "216") (name "unconnected-(E25-Pad10)") (class "Default")
      (node (ref "E25") (pin "10") (pinfunction "10_10") (pintype "passive"))
    )
    (net (code "217") (name "unconnected-(E25-Pad11)") (class "Default")
      (node (ref "E25") (pin "11") (pinfunction "11_11") (pintype "passive"))
    )
    (net (code "218") (name "unconnected-(E25-Pad12)") (class "Default")
      (node (ref "E25") (pin "12") (pinfunction "12_12") (pintype "passive"))
    )
    (net (code "219") (name "unconnected-(E25-Pad13)") (class "Default")
      (node (ref "E25") (pin "13") (pinfunction "13_13") (pintype "passive"))
    )
    (net (code "220") (name "unconnected-(E29A-Q2-Pad9)") (class "Default")
      (node (ref "E29") (pin "9") (pinfunction "Q2_9") (pintype "output"))
    )
    (net (code "221") (name "unconnected-(E29A-Q3-Pad11)") (class "Default")
      (node (ref "E29") (pin "11") (pinfunction "Q3_11") (pintype "output"))
    )
    (net (code "222") (name "unconnected-(E29A-Q4-Pad12)") (class "Default")
      (node (ref "E29") (pin "12") (pinfunction "Q4_12") (pintype "output"))
    )
    (net (code "223") (name "unconnected-(E36A-QB-Pad9)") (class "Default")
      (node (ref "E36") (pin "9") (pinfunction "QB_9") (pintype "output"))
    )
    (net (code "224") (name "unconnected-(E36A-QC-Pad8)") (class "Default")
      (node (ref "E36") (pin "8") (pinfunction "QC_8") (pintype "output"))
    )
    (net (code "225") (name "unconnected-(E40A-I3-Pad4)") (class "Default")
      (node (ref "E40") (pin "4") (pinfunction "I3_4") (pintype "input"))
    )
    (net (code "226") (name "unconnected-(E40A-I5-Pad6)") (class "Default")
      (node (ref "E40") (pin "6") (pinfunction "I5_6") (pintype "input"))
    )
    (net (code "227") (name "unconnected-(E45A-0-Pad13)") (class "Default")
      (node (ref "E45") (pin "13") (pinfunction "0_13") (pintype "output"))
    )
    (net (code "228") (name "unconnected-(E45A-8-Pad6)") (class "Default")
      (node (ref "E45") (pin "6") (pinfunction "8_6") (pintype "output"))
    )
    (net (code "229") (name "unconnected-(E45A-9-Pad7)") (class "Default")
      (node (ref "E45") (pin "7") (pinfunction "9_7") (pintype "output"))
    )
    (net (code "230") (name "unconnected-(J1-14-PadR)") (class "Default")
      (node (ref "J1") (pin "R") (pinfunction "14_R") (pintype "bidirectional"))
    )
    (net (code "231") (name "~{CC_67X}") (class "Default")
      (node (ref "E07") (pin "11") (pinfunction "I0_11") (pintype "input"))
      (node (ref "E07") (pin "5") (pinfunction "I1_5") (pintype "input"))
      (node (ref "E07") (pin "6") (pinfunction "I0_6") (pintype "input"))
      (node (ref "E07") (pin "9") (pinfunction "I0_9") (pintype "input"))
      (node (ref "E12") (pin "10") (pinfunction "I1_10") (pintype "input"))
      (node (ref "E12") (pin "11") (pinfunction "I0_11") (pintype "input"))
      (node (ref "E12") (pin "4") (pinfunction "I0_4") (pintype "input"))
      (node (ref "E12") (pin "6") (pinfunction "I0_6") (pintype "input"))
      (node (ref "E17") (pin "11") (pinfunction "I0_11") (pintype "input"))
      (node (ref "E17") (pin "4") (pinfunction "I0_4") (pintype "input"))
      (node (ref "E17") (pin "6") (pinfunction "I0_6") (pintype "input"))
      (node (ref "E17") (pin "9") (pinfunction "I0_9") (pintype "input"))
      (node (ref "E26") (pin "10") (pinfunction "O_10") (pintype "output"))
      (node (ref "E44") (pin "10") (pinfunction "I1_10") (pintype "input"))
      (node (ref "E44") (pin "12") (pinfunction "I1_12") (pintype "input"))
      (node (ref "E44") (pin "6") (pinfunction "I0_6") (pintype "input"))
      (node (ref "E45") (pin "2") (pinfunction "D_2") (pintype "input"))
      (node (ref "R6") (pin "1") (pinfunction "1_1") (pintype "passive"))
    )
    (net (code "232") (name "~{CC_CLK_TE}") (class "Default")
      (node (ref "E26") (pin "6") (pinfunction "O_6") (pintype "output"))
      (node (ref "E27") (pin "2") (pinfunction "I1_2") (pintype "input"))
    )
    (net (code "233") (name "~{CC_DTP0}") (class "Default")
      (node (ref "E22") (pin "2") (pinfunction "I1_2") (pintype "input"))
      (node (ref "E31") (pin "13") (pinfunction "I_13") (pintype "input"))
      (node (ref "E31") (pin "4") (pinfunction "O_4") (pintype "output"))
      (node (ref "E38") (pin "13") (pinfunction "I1_13") (pintype "input"))
    )
    (net (code "234") (name "~{CC_DTP1}") (class "Default")
      (node (ref "E22") (pin "12") (pinfunction "I0_12") (pintype "input"))
      (node (ref "E22") (pin "5") (pinfunction "I1_5") (pintype "input"))
      (node (ref "E22") (pin "9") (pinfunction "I0_9") (pintype "input"))
      (node (ref "E31") (pin "2") (pinfunction "O_2") (pintype "output"))
    )
    (net (code "235") (name "~{CC_INIT}") (class "Default")
      (node (ref "E27") (pin "1") (pinfunction "I0_1") (pintype "input"))
      (node (ref "E32") (pin "10") (pinfunction "O_10") (pintype "output"))
      (node (ref "E34") (pin "1") (pinfunction "CLR_1") (pintype "input"))
      (node (ref "E34") (pin "13") (pinfunction "CLR_13") (pintype "input"))
      (node (ref "E40") (pin "12") (pinfunction "I7_12") (pintype "input"))
    )
    (net (code "236") (name "~{CC_RUN}") (class "Default")
      (node (ref "E20") (pin "14") (pinfunction "O_14") (pintype "output"))
      (node (ref "E26") (pin "13") (pinfunction "I_13") (pintype "input"))
      (node (ref "E40") (pin "3") (pinfunction "I2_3") (pintype "input"))
    )
    (net (code "237") (name "~{CC_SDLC}") (class "Default")
      (node (ref "E19") (pin "13") (pinfunction "I1_13") (pintype "input"))
      (node (ref "E37") (pin "12") (pinfunction "I1_12") (pintype "input"))
      (node (ref "E45") (pin "9") (pinfunction "4_9") (pintype "output"))
    )
    (net (code "238") (name "~{CC_SDLD}") (class "Default")
      (node (ref "E02") (pin "3") (pinfunction "I1_3") (pintype "input"))
      (node (ref "E06") (pin "13") (pinfunction "S_13") (pintype "input"))
      (node (ref "E11") (pin "13") (pinfunction "S_13") (pintype "input"))
      (node (ref "E16") (pin "13") (pinfunction "S_13") (pintype "input"))
      (node (ref "E27") (pin "5") (pinfunction "I2_5") (pintype "input"))
      (node (ref "E33") (pin "12") (pinfunction "I1_12") (pintype "input"))
      (node (ref "E45") (pin "3") (pinfunction "5_3") (pintype "output"))
    )
    (net (code "239") (name "~{CC_SDRC}") (class "Default")
      (node (ref "E05") (pin "9") (pinfunction "S0_9") (pintype "input"))
      (node (ref "E10") (pin "9") (pinfunction "S0_9") (pintype "input"))
      (node (ref "E15") (pin "9") (pinfunction "S0_9") (pintype "input"))
      (node (ref "E27") (pin "3") (pinfunction "I0_3") (pintype "input"))
      (node (ref "E45") (pin "4") (pinfunction "6_4") (pintype "output"))
    )
    (net (code "240") (name "~{CC_SDRD}") (class "Default")
      (node (ref "E05") (pin "7") (pinfunction "S1_7") (pintype "input"))
      (node (ref "E10") (pin "7") (pinfunction "S1_7") (pintype "input"))
      (node (ref "E15") (pin "7") (pinfunction "S1_7") (pintype "input"))
      (node (ref "E27") (pin "4") (pinfunction "I1_4") (pintype "input"))
      (node (ref "E45") (pin "5") (pinfunction "7_5") (pintype "output"))
    )
    (net (code "241") (name "~{CC_SDSQ}") (class "Default")
      (node (ref "E32") (pin "1") (pinfunction "I_1") (pintype "input"))
      (node (ref "E45") (pin "10") (pinfunction "3_10") (pintype "output"))
    )
    (net (code "242") (name "~{CC_SDSS}") (class "Default")
      (node (ref "E32") (pin "3") (pinfunction "I_3") (pintype "input"))
      (node (ref "E45") (pin "12") (pinfunction "1_12") (pintype "output"))
    )
    (net (code "243") (name "~{CC_SDST}") (class "Default")
      (node (ref "E32") (pin "5") (pinfunction "I_5") (pintype "input"))
      (node (ref "E45") (pin "11") (pinfunction "2_11") (pintype "output"))
    )
    (net (code "244") (name "~{CC_SETDLY}") (class "Default")
      (node (ref "E03") (pin "5") (pinfunction "Q_5") (pintype "output"))
      (node (ref "E22") (pin "4") (pinfunction "I0_4") (pintype "input"))
    )
    (net (code "245") (name "~{CC_TP3}") (class "Default")
      (node (ref "E01") (pin "1") (pinfunction "I_1") (pintype "input"))
      (node (ref "E02") (pin "2") (pinfunction "I0_2") (pintype "input"))
      (node (ref "E20") (pin "13") (pinfunction "O_13") (pintype "output"))
      (node (ref "E37") (pin "11") (pinfunction "I0_11") (pintype "input"))
    )
    (net (code "246") (name "~{CC_TPG1}") (class "Default")
      (node (ref "E14") (pin "6") (pinfunction "~{Q}_6") (pintype "output"))
      (node (ref "E42") (pin "1") (pinfunction "I0_1") (pintype "input"))
    )
    (net (code "247") (name "~{CC_TPG_CLK}") (class "Default")
      (node (ref "C40") (pin "1") (pinfunction "1_1") (pintype "passive"))
      (node (ref "E04") (pin "10") (pinfunction "B_10") (pintype "input"))
      (node (ref "R25") (pin "1") (pinfunction "1_1") (pintype "passive"))
    )
    (net (code "248") (name "~{CC_UNIT}") (class "Default")
      (node (ref "E05") (pin "11") (pinfunction "B2_11") (pintype "input"))
      (node (ref "E34") (pin "8") (pinfunction "~{Q}_8") (pintype "output"))
    )
    (net (code "249") (name "~{CC_UTS}") (class "Default")
      (node (ref "E02") (pin "11") (pinfunction "I0_11") (pintype "input"))
      (node (ref "E03") (pin "8") (pinfunction "~{Q}_8") (pintype "output"))
    )
    (net (code "250") (name "~{DF_HLD}") (class "Default")
      (node (ref "E10") (pin "11") (pinfunction "B2_11") (pintype "input"))
      (node (ref "E32") (pin "8") (pinfunction "O_8") (pintype "output"))
      (node (ref "E40") (pin "2") (pinfunction "I1_2") (pintype "input"))
    )
    (net (code "251") (name "~{DF_SEL_ER}") (class "Default")
      (node (ref "E32") (pin "13") (pinfunction "I_13") (pintype "input"))
      (node (ref "E40") (pin "5") (pinfunction "I4_5") (pintype "input"))
      (node (ref "Q2") (pin "3") (pinfunction "C_3") (pintype "passive"))
      (node (ref "Q3") (pin "3") (pinfunction "C_3") (pintype "passive"))
      (node (ref "R11") (pin "1") (pinfunction "1_1") (pintype "passive"))
    )
    (net (code "252") (name "~{DF_TIME_ER}") (class "Default")
      (node (ref "E27") (pin "12") (pinfunction "O_12") (pintype "output"))
      (node (ref "E35") (pin "5") (pinfunction "I2_5") (pintype "input"))
      (node (ref "E40") (pin "1") (pinfunction "I0_1") (pintype "input"))
    )
    (net (code "253") (name "~{MTR0}") (class "Default")
      (node (ref "E10") (pin "5") (pinfunction "B1_5") (pintype "input"))
      (node (ref "E29") (pin "7") (pinfunction "Q1_7") (pintype "output"))
    )
    (net (code "254") (name "~{MTR1}") (class "Default")
      (node (ref "E10") (pin "2") (pinfunction "B0_2") (pintype "input"))
      (node (ref "E29") (pin "5") (pinfunction "Q0_5") (pintype "output"))
    )
    (net (code "255") (name "~{MTR2}") (class "Default")
      (node (ref "E15") (pin "11") (pinfunction "B2_11") (pintype "input"))
      (node (ref "E21") (pin "11") (pinfunction "Q3_11") (pintype "output"))
      (node (ref "E29") (pin "4") (pinfunction "D_4") (pintype "input"))
    )
    (net (code "256") (name "~{MTR3}") (class "Default")
      (node (ref "E15") (pin "14") (pinfunction "B3_14") (pintype "input"))
      (node (ref "E21") (pin "9") (pinfunction "Q2_9") (pintype "output"))
    )
    (net (code "257") (name "~{MTR4}") (class "Default")
      (node (ref "E15") (pin "5") (pinfunction "B1_5") (pintype "input"))
      (node (ref "E21") (pin "7") (pinfunction "Q1_7") (pintype "output"))
    )
    (net (code "258") (name "~{MTR5}") (class "Default")
      (node (ref "E15") (pin "2") (pinfunction "B0_2") (pintype "input"))
      (node (ref "E21") (pin "5") (pinfunction "Q0_5") (pintype "output"))
    )
    (net (code "259") (name "~{POWER_OK}") (class "Default")
      (node (ref "E28") (pin "6") (pinfunction "I0_6") (pintype "input"))
      (node (ref "EDGE$") (pin "BV2") (pinfunction "1_BV2") (pintype "bidirectional"))
    )
    (net (code "260") (name "~{RTT}") (class "Default")
      (node (ref "E42") (pin "6") (pinfunction "I1_6") (pintype "input"))
      (node (ref "J1") (pin "J") (pinfunction "8_J") (pintype "bidirectional"))
      (node (ref "R18") (pin "1") (pinfunction "1_1") (pintype "passive"))
    )
    (net (code "261") (name "~{SKIP}") (class "Default")
      (node (ref "E41") (pin "1") (pinfunction "O_1") (pintype "open_collector"))
      (node (ref "E41") (pin "10") (pinfunction "O_10") (pintype "open_collector"))
      (node (ref "E41") (pin "13") (pinfunction "O_13") (pintype "open_collector"))
      (node (ref "EDGE$") (pin "CS1") (pinfunction "1_CS1") (pintype "bidirectional"))
    )
  )
)
